# 16F.net
KiCad netlist of a schematic drawn in EasyEDA Pro
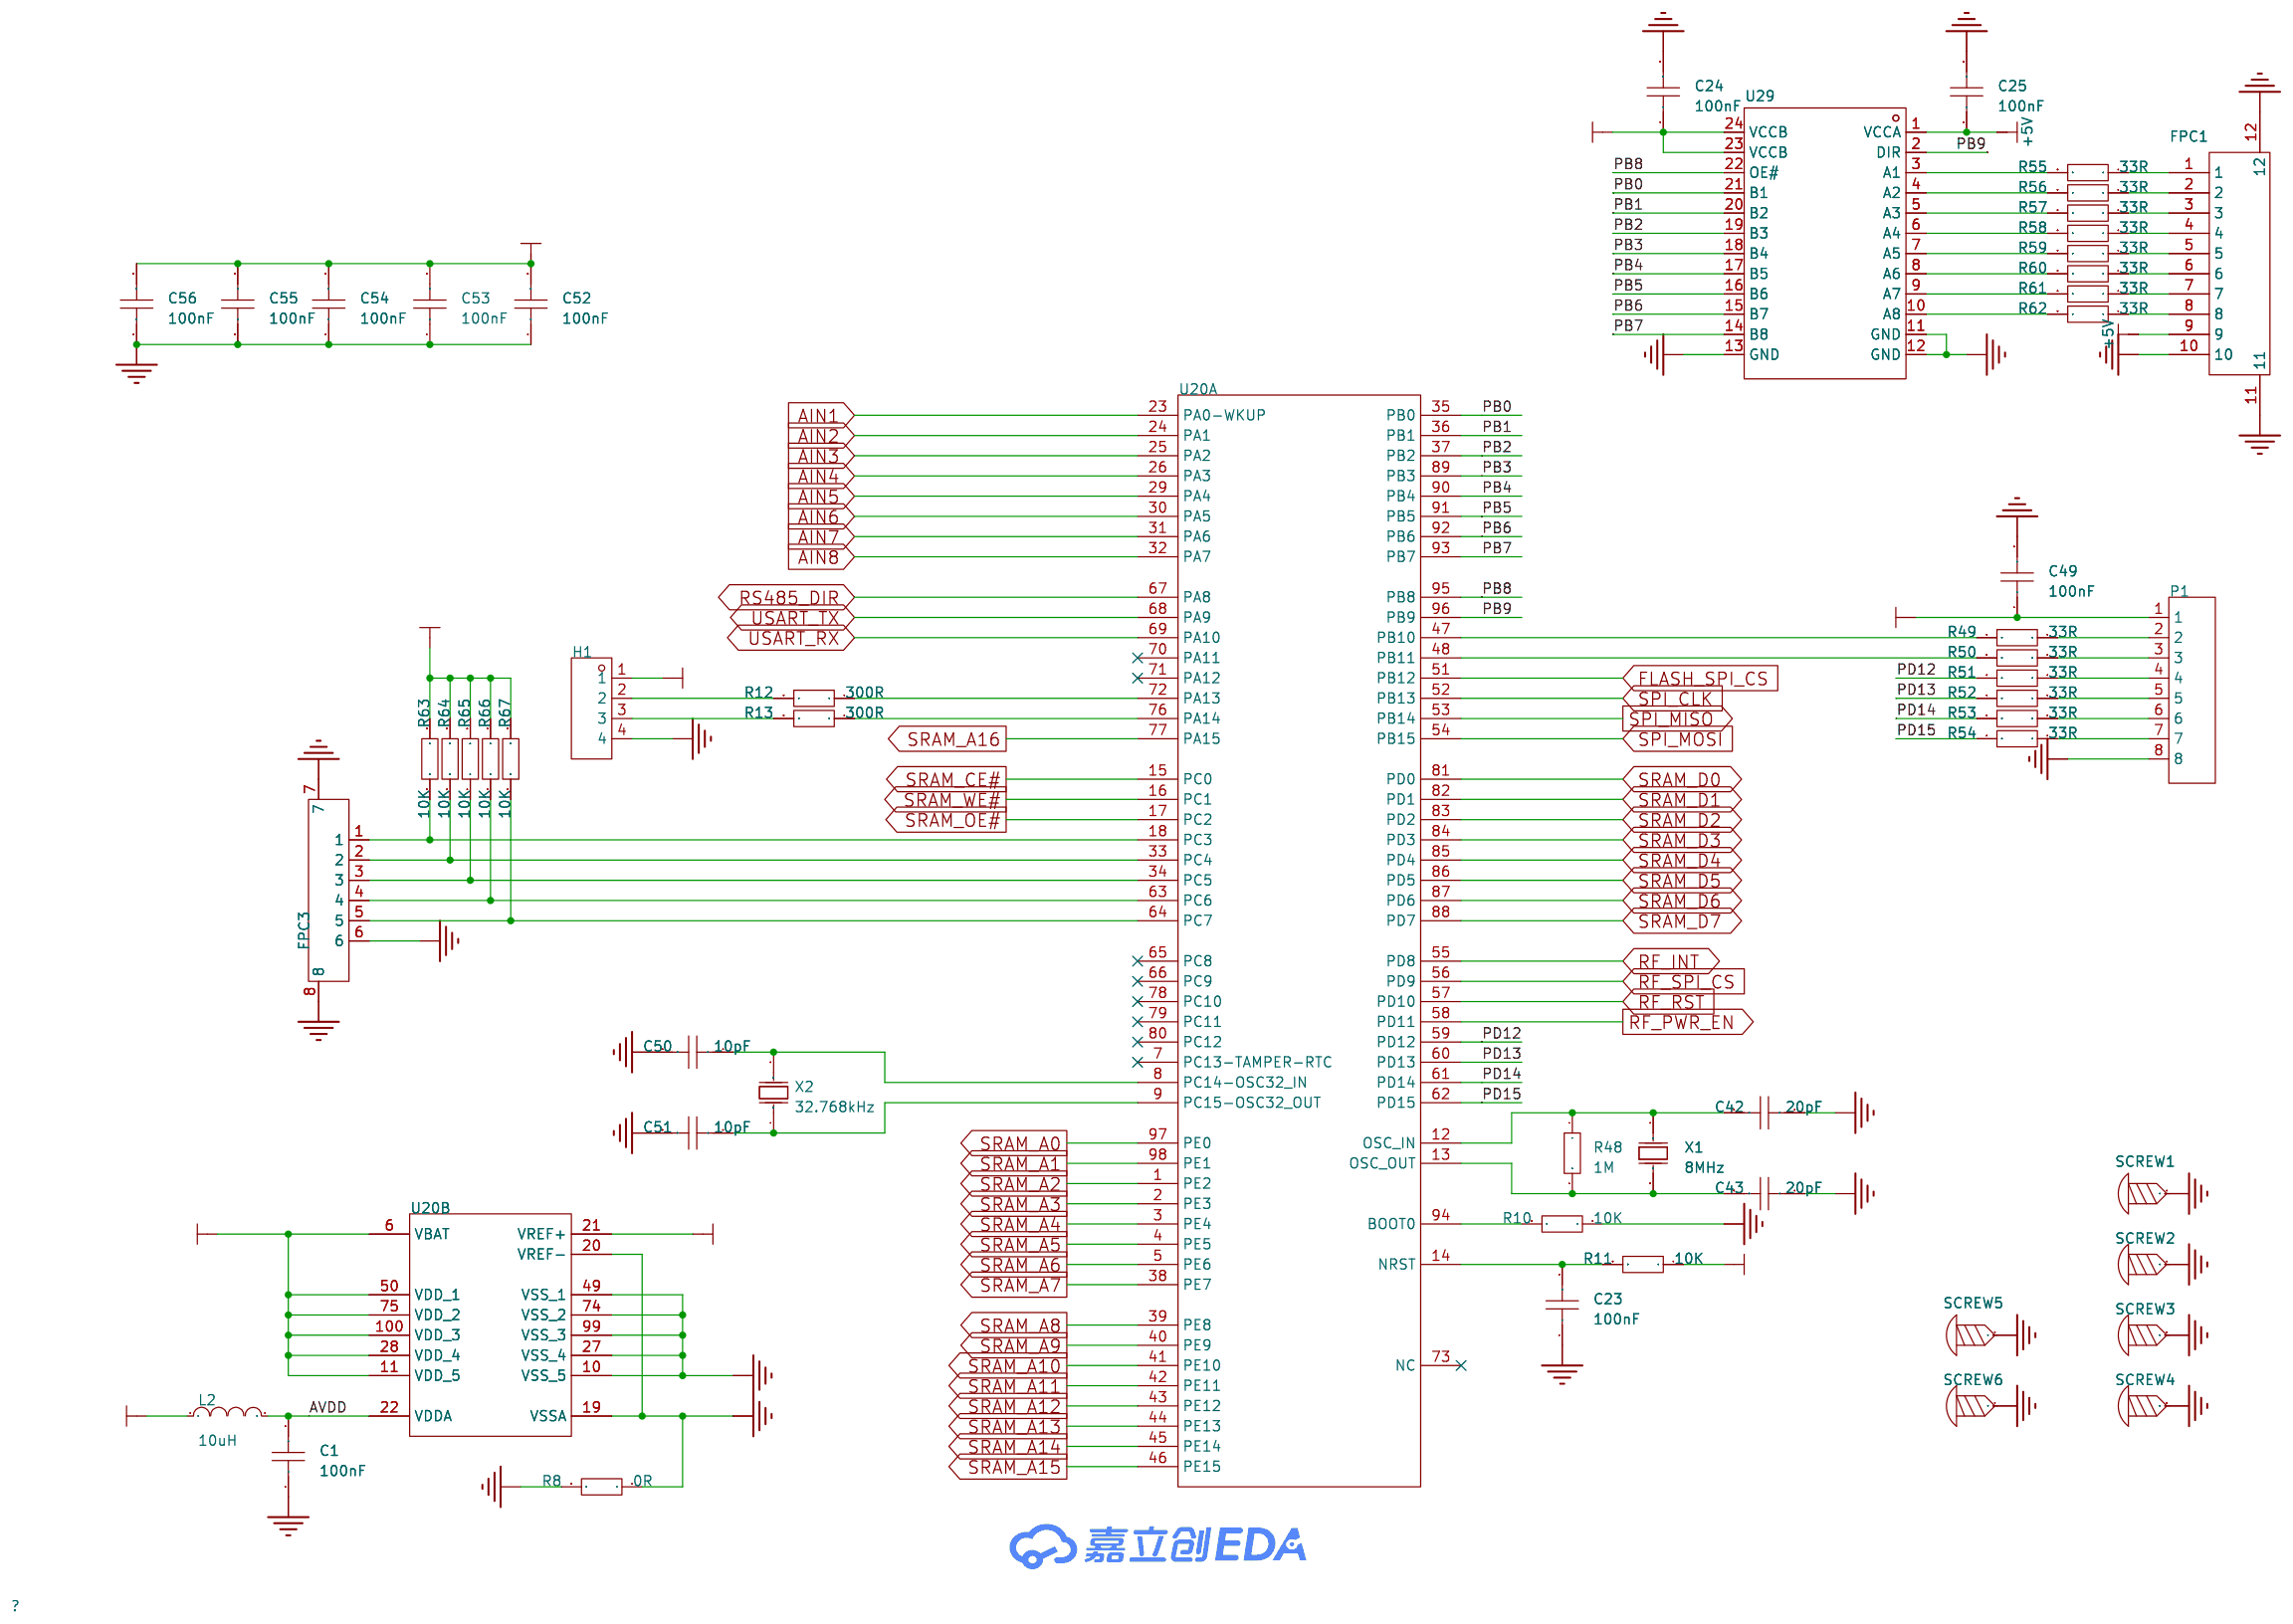
[diagram p0: MCU]
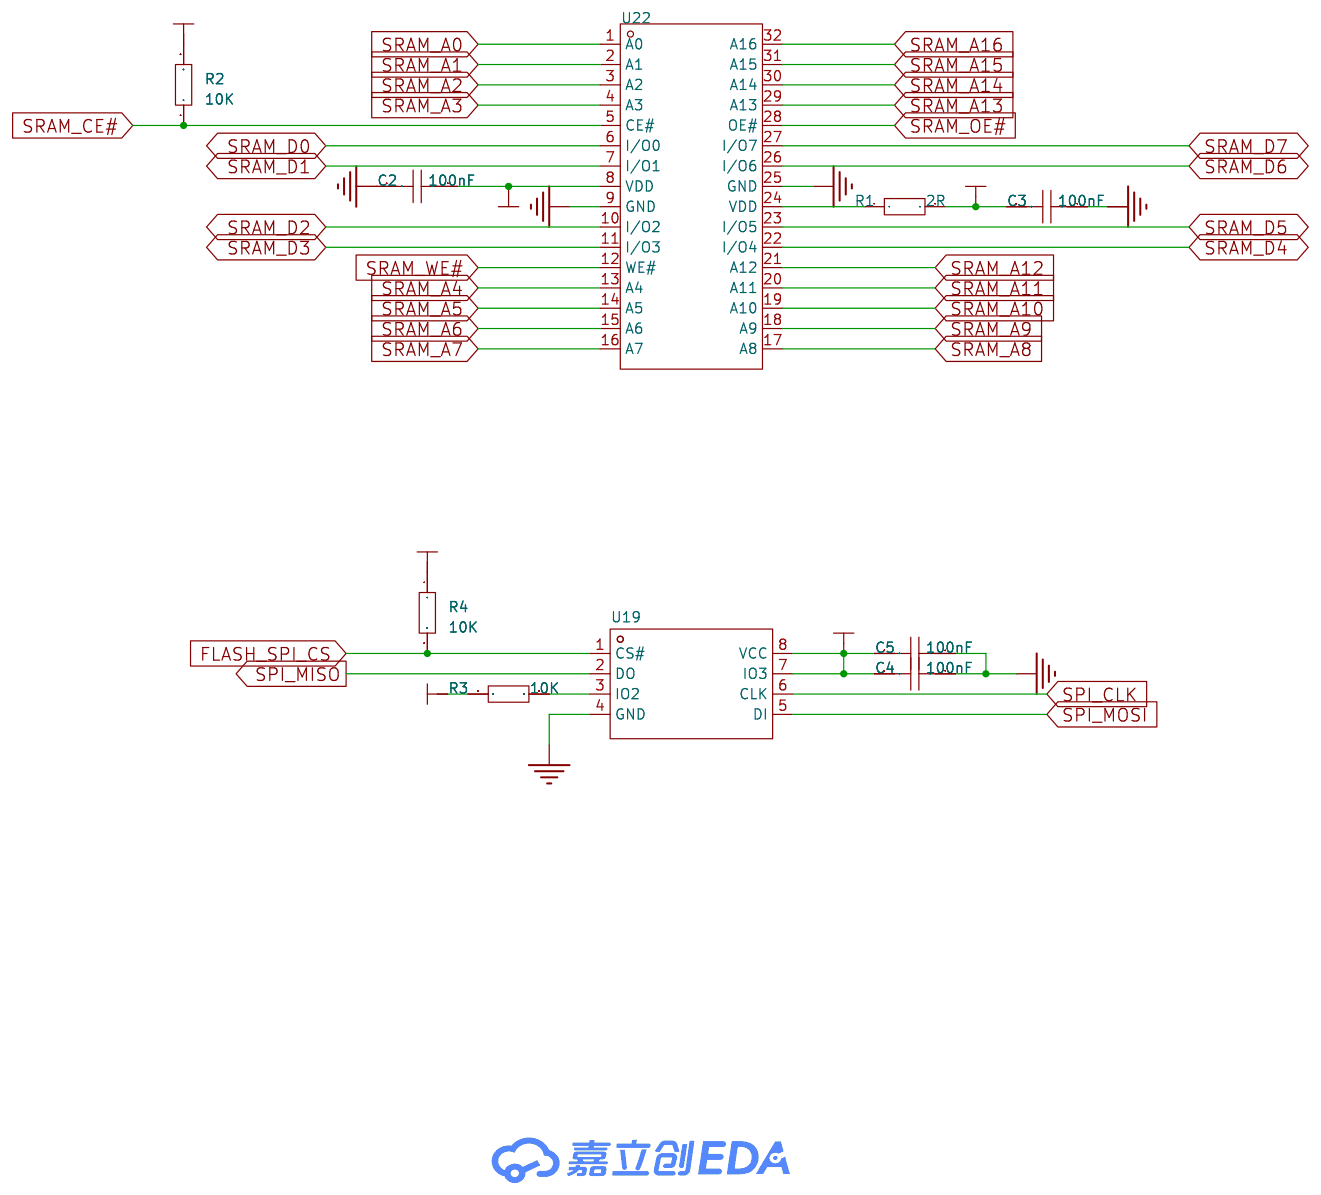
[diagram p1: MEM]
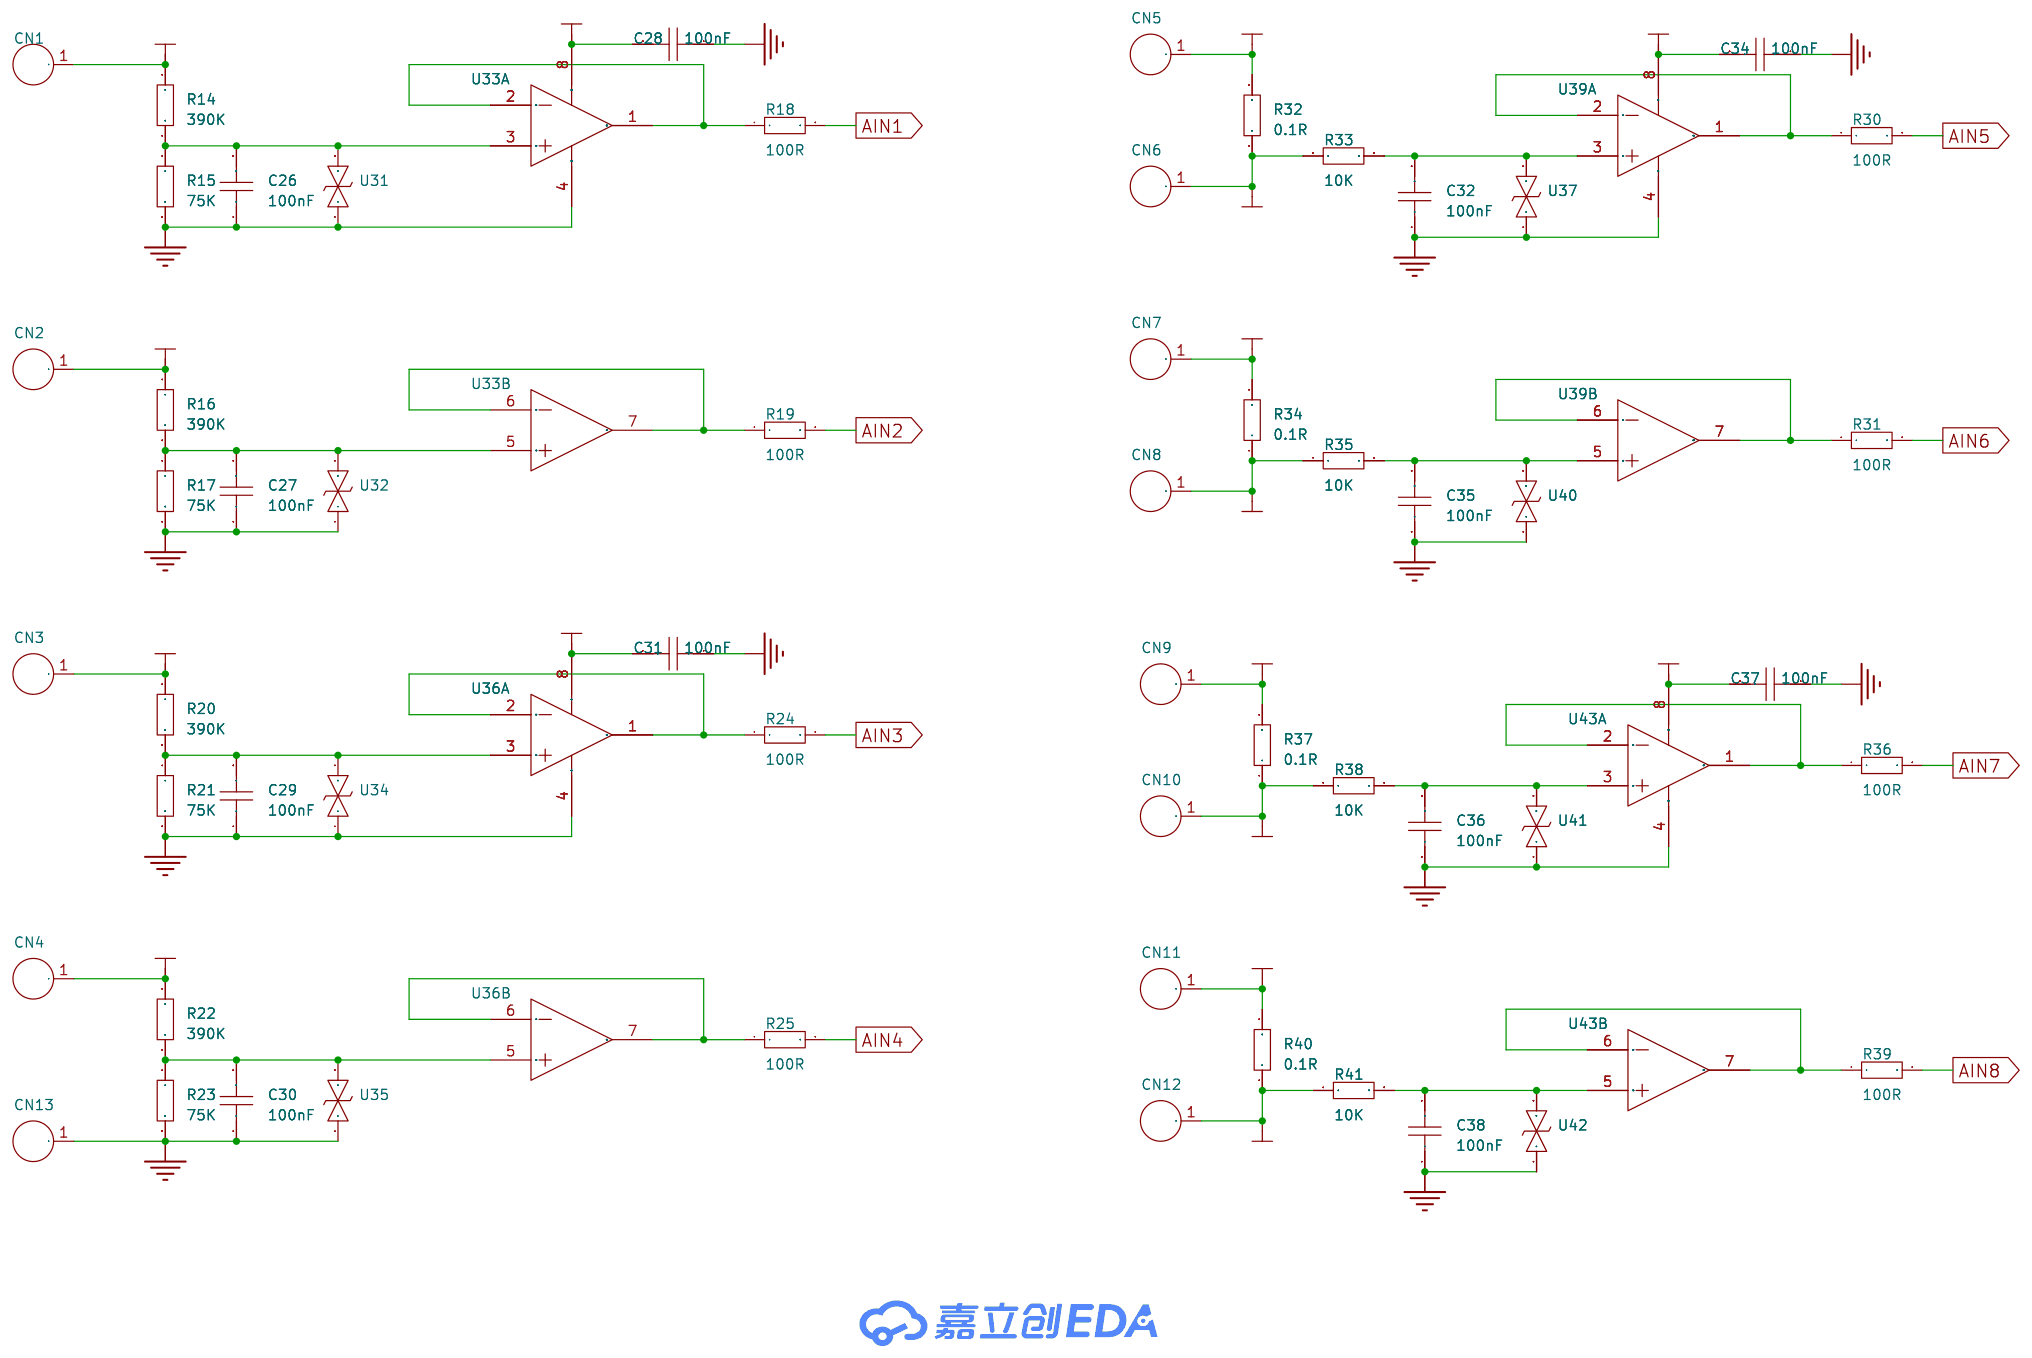
[diagram p2: AIN]
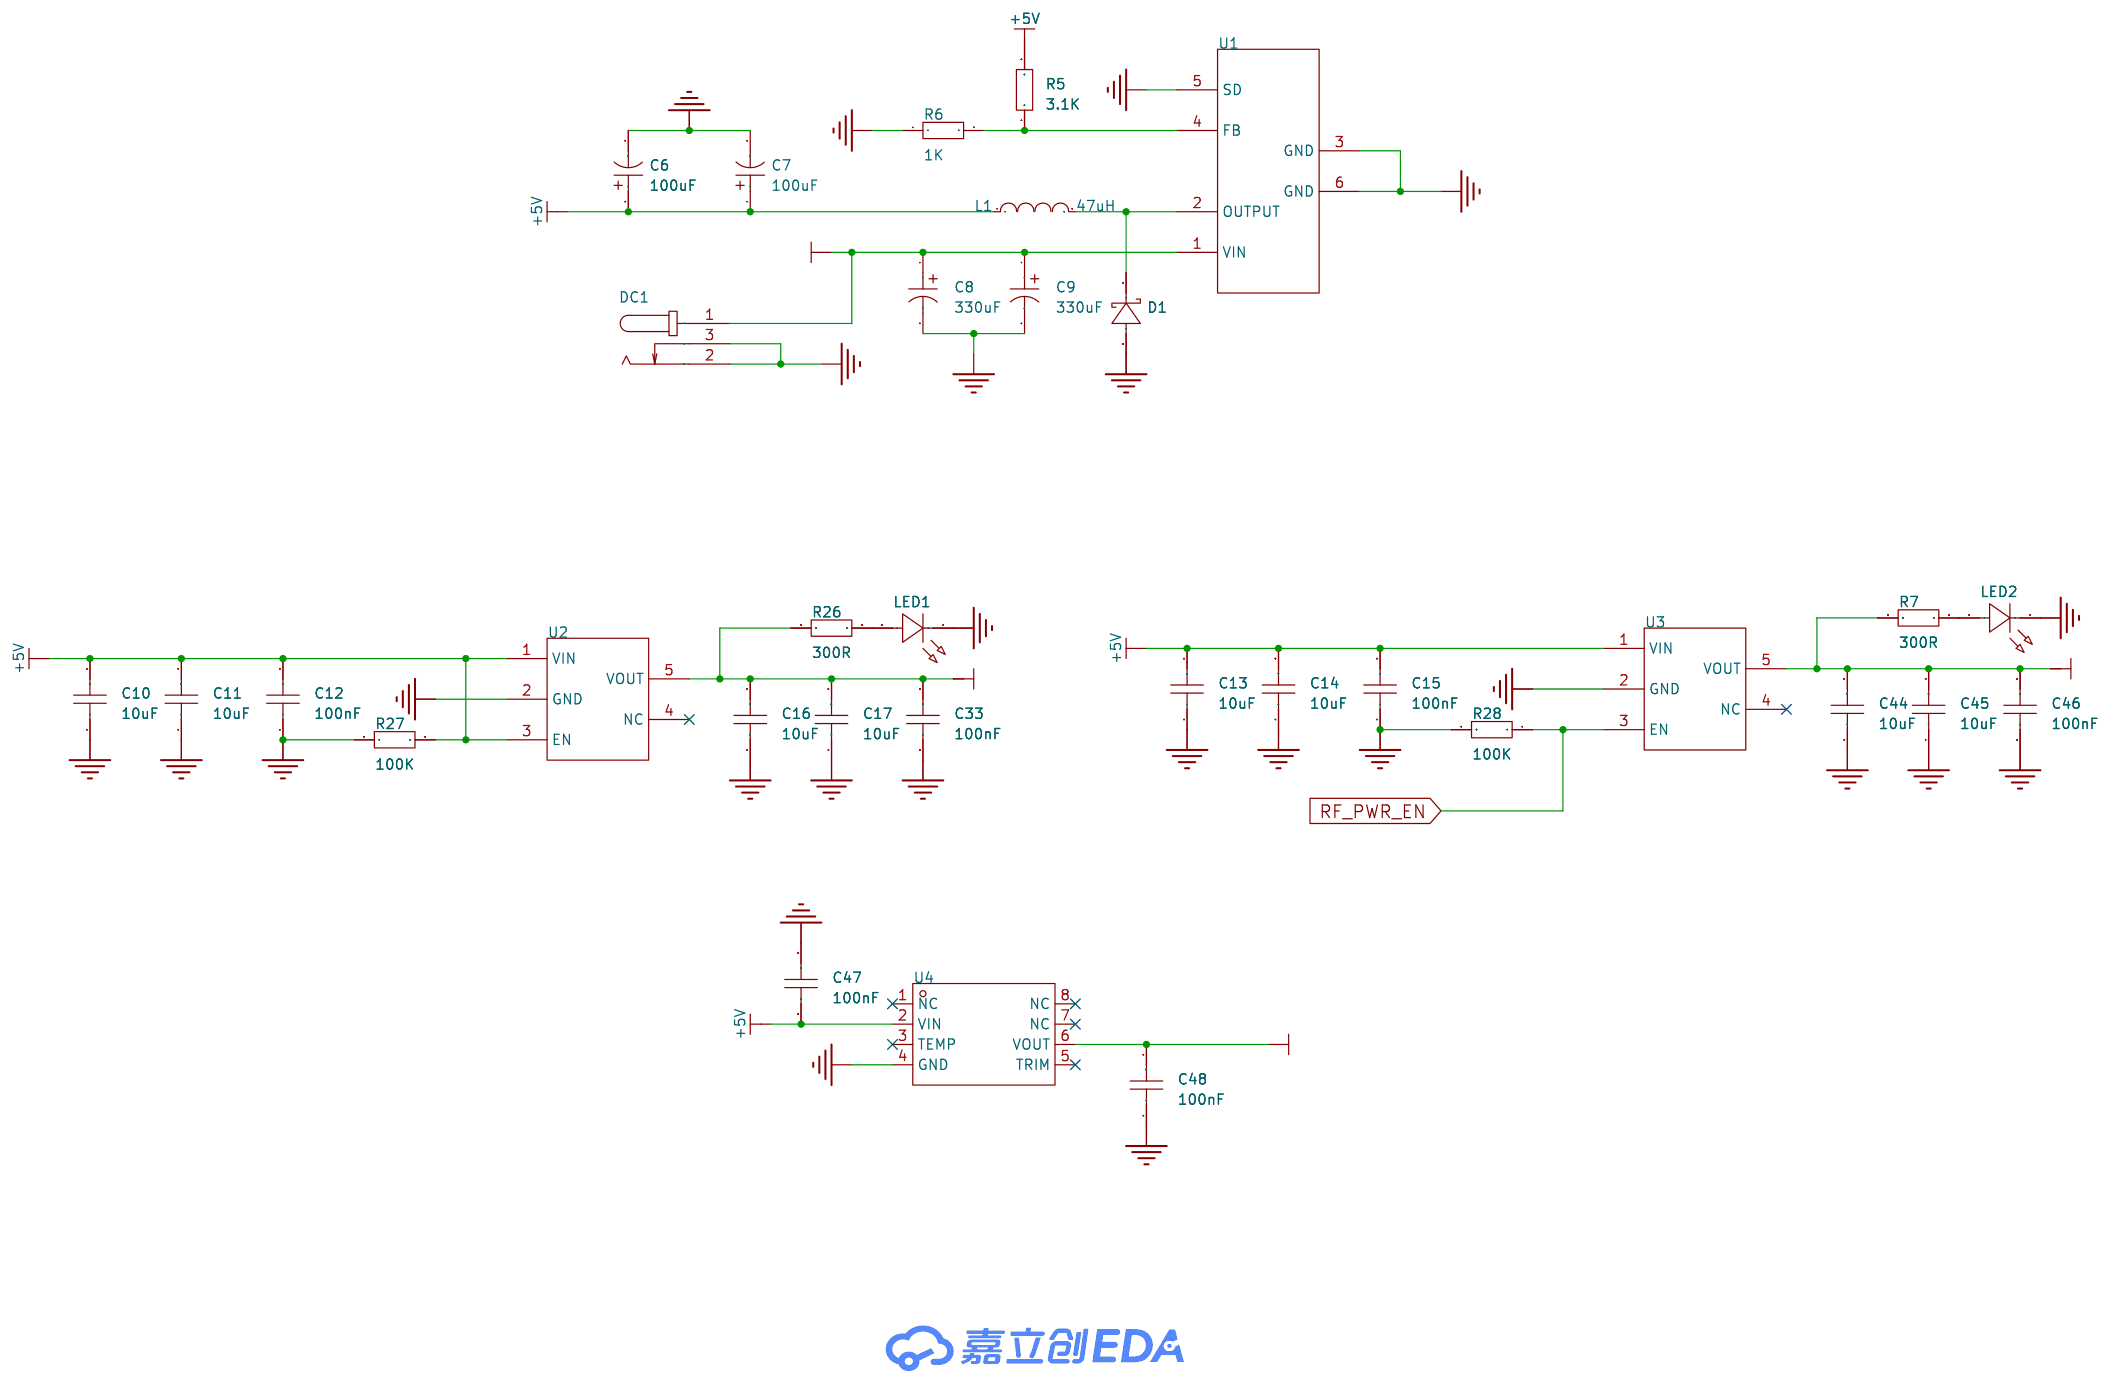
[diagram p3: POWER]
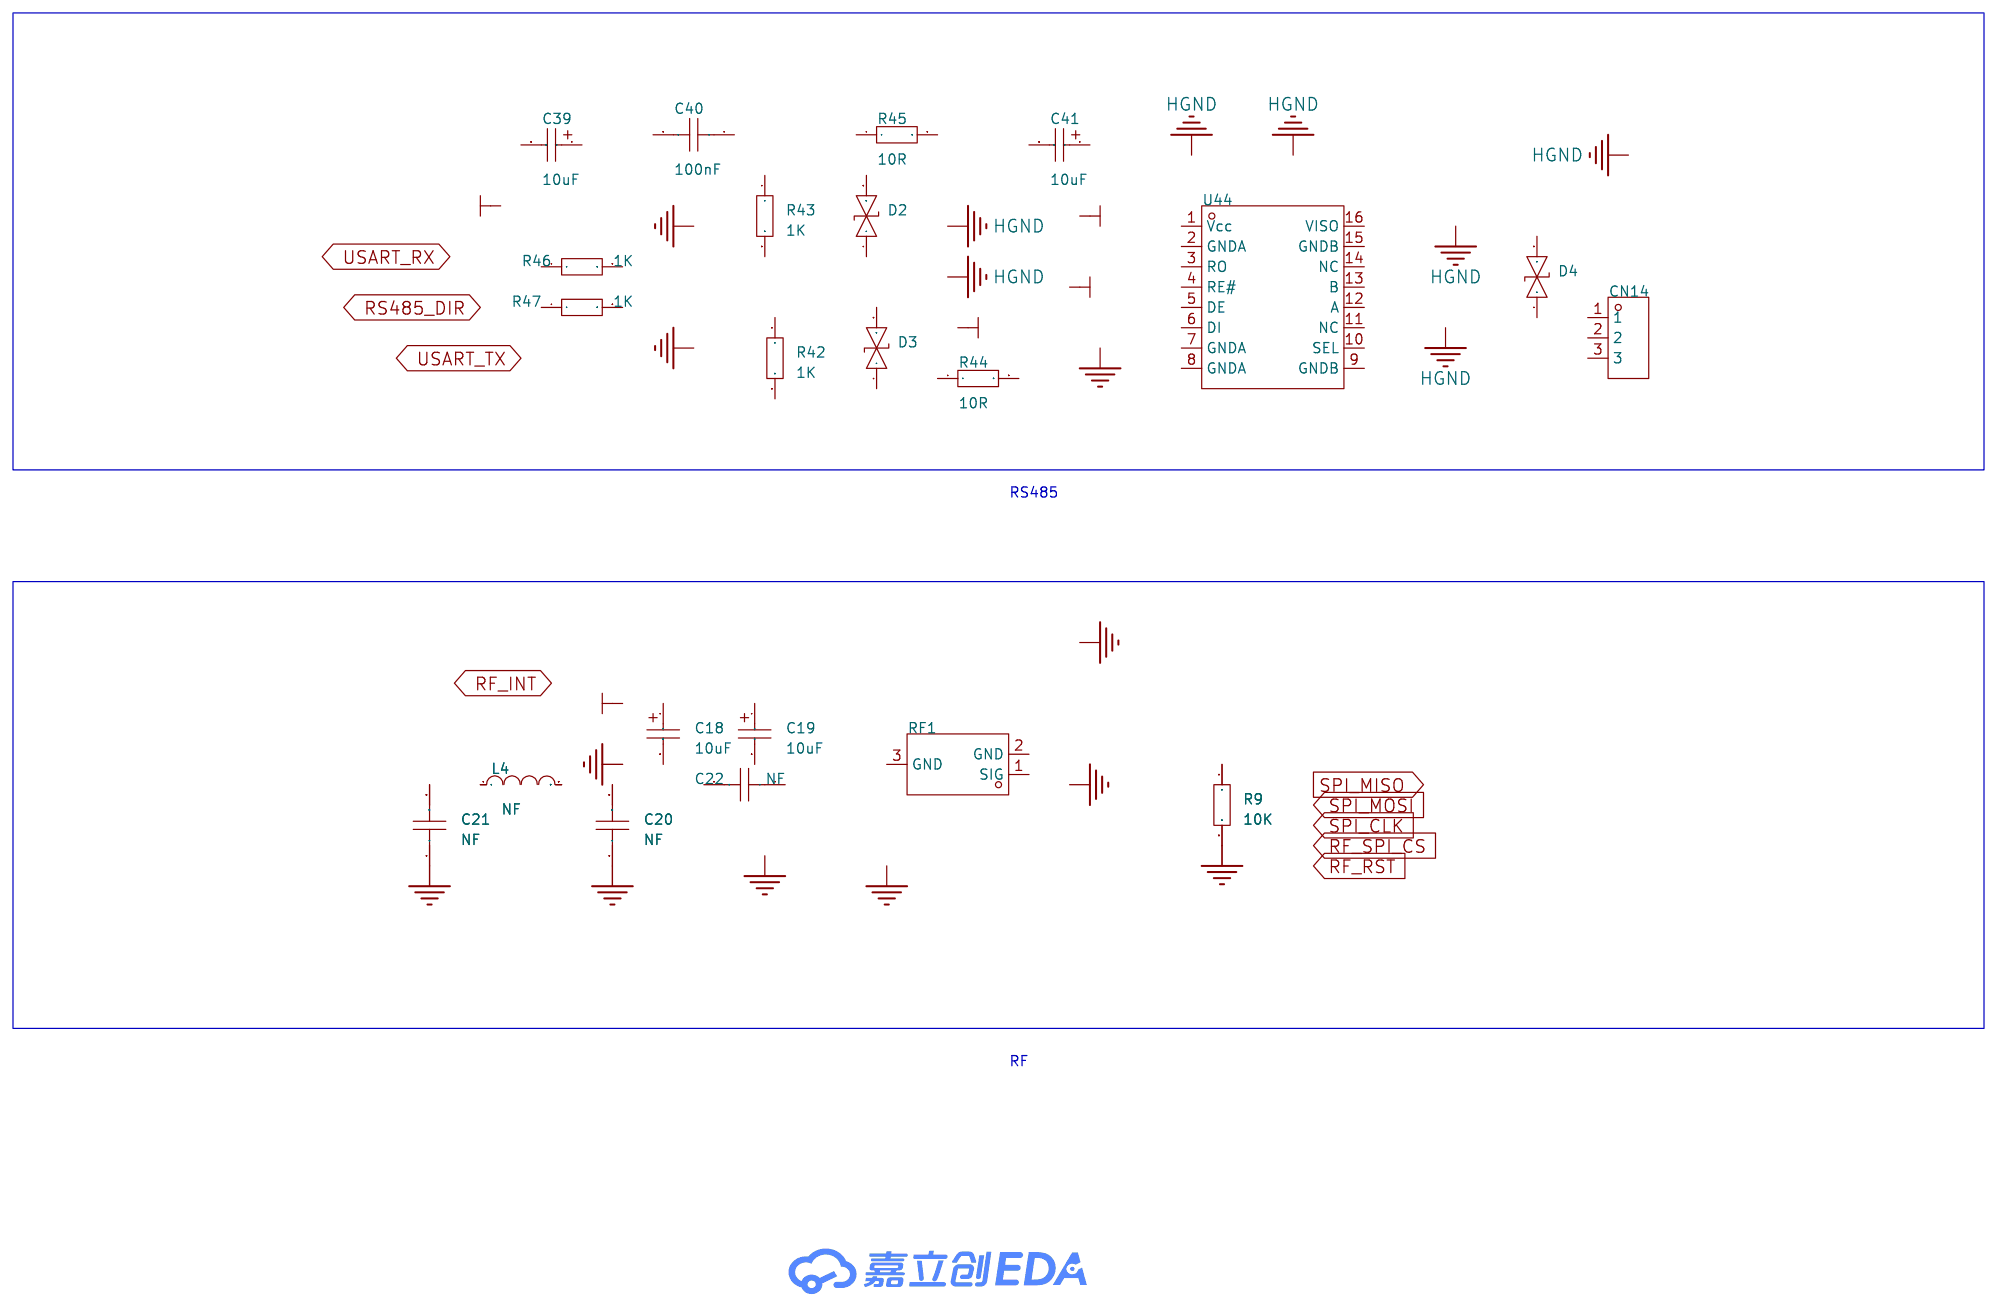
[diagram p4: RF]

(export (version "E")
  (design (tool "Eeschema 10.0.6"))
  (components
    (comp (ref "C1")
      (value "100nF")
      (footprint "easyedapro:C0805")
      (libsource (lib "easyedapro") (part "CapAcitance"))
    )
    (comp (ref "C23")
      (value "100nF")
      (footprint "easyedapro:C0805")
      (libsource (lib "easyedapro") (part "CapAcitance"))
    )
    (comp (ref "C24")
      (value "100nF")
      (footprint "easyedapro:C0805")
      (libsource (lib "easyedapro") (part "CapAcitance"))
    )
    (comp (ref "C25")
      (value "100nF")
      (footprint "easyedapro:C0805")
      (libsource (lib "easyedapro") (part "CapAcitance"))
    )
    (comp (ref "C42")
      (value "20pF")
      (footprint "easyedapro:C0805")
      (libsource (lib "easyedapro") (part "CapAcitance"))
    )
    (comp (ref "C43")
      (value "20pF")
      (footprint "easyedapro:C0805")
      (libsource (lib "easyedapro") (part "CapAcitance"))
    )
    (comp (ref "C49")
      (value "100nF")
      (footprint "easyedapro:C0805")
      (libsource (lib "easyedapro") (part "CapAcitance"))
    )
    (comp (ref "C50")
      (value "10pF")
      (footprint "easyedapro:C0805")
      (libsource (lib "easyedapro") (part "CapAcitance"))
    )
    (comp (ref "C51")
      (value "10pF")
      (footprint "easyedapro:C0805")
      (libsource (lib "easyedapro") (part "CapAcitance"))
    )
    (comp (ref "C52")
      (value "100nF")
      (footprint "easyedapro:C0805")
      (libsource (lib "easyedapro") (part "CapAcitance"))
    )
    (comp (ref "C53")
      (value "100nF")
      (footprint "easyedapro:C0805")
      (libsource (lib "easyedapro") (part "CapAcitance"))
    )
    (comp (ref "C54")
      (value "100nF")
      (footprint "easyedapro:C0805")
      (libsource (lib "easyedapro") (part "CapAcitance"))
    )
    (comp (ref "C55")
      (value "100nF")
      (footprint "easyedapro:C0805")
      (libsource (lib "easyedapro") (part "CapAcitance"))
    )
    (comp (ref "C56")
      (value "100nF")
      (footprint "easyedapro:C0805")
      (libsource (lib "easyedapro") (part "CapAcitance"))
    )
    (comp (ref "FPC1")
      (value "AFA07-S10FCA-00")
      (footprint "easyedapro:FPC-SMD_P1.00-10P_LCS-XJ-H2.0")
      (fields (field (name "Manufacturer") "JS(钜硕电子)"))
      (libsource (lib "easyedapro") (part "AFA07-S10FCA-00"))
    )
    (comp (ref "FPC3")
      (value "FPC1.0-2H-WS-6P")
      (footprint "easyedapro:FPC-SMD_6P-P1.00_FPC1.0-2H-WS")
      (libsource (lib "easyedapro") (part "FPC1.0-2H-WS-6P"))
    )
    (comp (ref "H1")
      (value "~")
      (footprint "easyedapro:HDR-TH_4P-P2.54-V-F")
      (libsource (lib "easyedapro") (part "2.54-1*4P母"))
    )
    (comp (ref "L2")
      (value "10uH")
      (footprint "easyedapro:L0805")
      (libsource (lib "easyedapro") (part "SDFL2012S100KTF"))
    )
    (comp (ref "P1")
      (value "1.25T-8AW")
      (footprint "easyedapro:CONN-TH_8P-P1.25_1.25T-1-8AW")
      (fields (field (name "Manufacturer") "BOOMELE(博穆精密)"))
      (libsource (lib "easyedapro") (part "1.25T-1-8AW"))
    )
    (comp (ref "R8") (value "0R") (footprint "easyedapro:R1210") (libsource (lib "easyedapro") (part "电阻")))
    (comp (ref "R10") (value "10K") (footprint "easyedapro:R1210") (libsource (lib "easyedapro") (part "电阻")))
    (comp (ref "R11") (value "10K") (footprint "easyedapro:R1210") (libsource (lib "easyedapro") (part "电阻")))
    (comp (ref "R12")
      (value "300R")
      (footprint "easyedapro:R1210")
      (libsource (lib "easyedapro") (part "电阻"))
    )
    (comp (ref "R13")
      (value "300R")
      (footprint "easyedapro:R1210")
      (libsource (lib "easyedapro") (part "电阻"))
    )
    (comp (ref "R48") (value "1M") (footprint "easyedapro:R1210") (libsource (lib "easyedapro") (part "电阻")))
    (comp (ref "R49") (value "33R") (footprint "easyedapro:R1210") (libsource (lib "easyedapro") (part "电阻")))
    (comp (ref "R50") (value "33R") (footprint "easyedapro:R1210") (libsource (lib "easyedapro") (part "电阻")))
    (comp (ref "R51") (value "33R") (footprint "easyedapro:R1210") (libsource (lib "easyedapro") (part "电阻")))
    (comp (ref "R52") (value "33R") (footprint "easyedapro:R1210") (libsource (lib "easyedapro") (part "电阻")))
    (comp (ref "R53") (value "33R") (footprint "easyedapro:R1210") (libsource (lib "easyedapro") (part "电阻")))
    (comp (ref "R54") (value "33R") (footprint "easyedapro:R1210") (libsource (lib "easyedapro") (part "电阻")))
    (comp (ref "R55") (value "33R") (footprint "easyedapro:R1210") (libsource (lib "easyedapro") (part "电阻")))
    (comp (ref "R56") (value "33R") (footprint "easyedapro:R1210") (libsource (lib "easyedapro") (part "电阻")))
    (comp (ref "R57") (value "33R") (footprint "easyedapro:R1210") (libsource (lib "easyedapro") (part "电阻")))
    (comp (ref "R58") (value "33R") (footprint "easyedapro:R1210") (libsource (lib "easyedapro") (part "电阻")))
    (comp (ref "R59") (value "33R") (footprint "easyedapro:R1210") (libsource (lib "easyedapro") (part "电阻")))
    (comp (ref "R60") (value "33R") (footprint "easyedapro:R1210") (libsource (lib "easyedapro") (part "电阻")))
    (comp (ref "R61") (value "33R") (footprint "easyedapro:R1210") (libsource (lib "easyedapro") (part "电阻")))
    (comp (ref "R62") (value "33R") (footprint "easyedapro:R1210") (libsource (lib "easyedapro") (part "电阻")))
    (comp (ref "R63") (value "10K") (footprint "easyedapro:R1210") (libsource (lib "easyedapro") (part "电阻")))
    (comp (ref "R64") (value "10K") (footprint "easyedapro:R1210") (libsource (lib "easyedapro") (part "电阻")))
    (comp (ref "R65") (value "10K") (footprint "easyedapro:R1210") (libsource (lib "easyedapro") (part "电阻")))
    (comp (ref "R66") (value "10K") (footprint "easyedapro:R1210") (libsource (lib "easyedapro") (part "电阻")))
    (comp (ref "R67") (value "10K") (footprint "easyedapro:R1210") (libsource (lib "easyedapro") (part "电阻")))
    (comp (ref "SCREW1")
      (value "~")
      (footprint "easyedapro:M2螺丝")
      (libsource (lib "easyedapro") (part "螺丝孔"))
    )
    (comp (ref "SCREW2")
      (value "~")
      (footprint "easyedapro:M2螺丝")
      (libsource (lib "easyedapro") (part "螺丝孔"))
    )
    (comp (ref "SCREW3")
      (value "~")
      (footprint "easyedapro:M2螺丝")
      (libsource (lib "easyedapro") (part "螺丝孔"))
    )
    (comp (ref "SCREW4")
      (value "~")
      (footprint "easyedapro:M2螺丝")
      (libsource (lib "easyedapro") (part "螺丝孔"))
    )
    (comp (ref "SCREW5")
      (value "~")
      (footprint "easyedapro:M2螺丝")
      (libsource (lib "easyedapro") (part "螺丝孔"))
    )
    (comp (ref "SCREW6")
      (value "~")
      (footprint "easyedapro:M2螺丝")
      (libsource (lib "easyedapro") (part "螺丝孔"))
    )
    (comp (ref "U20")
      (value "STM32F103VBT6")
      (footprint "easyedapro:LQFP-100_L14.0-W14.0-P0.50-LS16.0-BL")
      (fields (field (name "Manufacturer") "ST(意法半导体)"))
      (libsource (lib "easyedapro") (part "STM32F103VBT6"))
    )
    (comp (ref "U29")
      (value "SN74LVC8T245PWR")
      (footprint "easyedapro:TSSOP-24_L7.8-W4.4-P0.65-LS6.4-BL")
      (fields (field (name "Manufacturer") "TI(德州仪器)"))
      (libsource (lib "easyedapro") (part "SN74LVC8T245PWR"))
    )
    (comp (ref "X1")
      (value "8MHz")
      (footprint "easyedapro:CRYSTAL-SMD_L5.0-W3.2")
      (fields (field (name "Manufacturer Part") "X50328MSB2GI") (field (name "Manufacturer") "YXC(扬兴晶振)"))
      (libsource (lib "easyedapro") (part "X50328MSB2GI"))
    )
    (comp (ref "X2")
      (value "32.768kHz")
      (footprint "easyedapro:OSC-SMD_L3.2-W1.5")
      (fields (field (name "Manufacturer Part") "Q13FC1350000300") (field (name "Manufacturer") "EPSON(爱普生)"))
      (libsource (lib "easyedapro") (part "FC-13532.768KHZ9PF20PPM"))
    )
    (comp (ref "C2")
      (value "100nF")
      (footprint "easyedapro:C0805")
      (libsource (lib "easyedapro") (part "CapAcitance"))
    )
    (comp (ref "C3")
      (value "100nF")
      (footprint "easyedapro:C0805")
      (libsource (lib "easyedapro") (part "CapAcitance"))
    )
    (comp (ref "C4")
      (value "100nF")
      (footprint "easyedapro:C0805")
      (libsource (lib "easyedapro") (part "CapAcitance"))
    )
    (comp (ref "C5")
      (value "100nF")
      (footprint "easyedapro:C0805")
      (libsource (lib "easyedapro") (part "CapAcitance"))
    )
    (comp (ref "R1") (value "2R") (footprint "easyedapro:R1210") (libsource (lib "easyedapro") (part "电阻")))
    (comp (ref "R2") (value "10K") (footprint "easyedapro:R1210") (libsource (lib "easyedapro") (part "电阻")))
    (comp (ref "R3") (value "10K") (footprint "easyedapro:R1210") (libsource (lib "easyedapro") (part "电阻")))
    (comp (ref "R4") (value "10K") (footprint "easyedapro:R1210") (libsource (lib "easyedapro") (part "电阻")))
    (comp (ref "U19")
      (value "W25Q128JVSIQ")
      (footprint "easyedapro:SOIC-8_L5.3-W5.3-P1.27-LS8.0-BL")
      (fields (field (name "Manufacturer") "WINBOND(华邦)"))
      (libsource (lib "easyedapro") (part "W25Q128JVSIQTR"))
    )
    (comp (ref "U22")
      (value "IS63WV1288DBLL-10TLI")
      (footprint "easyedapro:TSOPII-32_L21.0-W10.2-P1.27-LS11.8-BL")
      (fields (field (name "Manufacturer") "ISSI(美国芯成)"))
      (libsource (lib "easyedapro") (part "IS63WV1288DBLL-10TLI"))
    )
    (comp (ref "C26")
      (value "100nF")
      (footprint "easyedapro:C0805")
      (libsource (lib "easyedapro") (part "CapAcitance"))
    )
    (comp (ref "C27")
      (value "100nF")
      (footprint "easyedapro:C0805")
      (libsource (lib "easyedapro") (part "CapAcitance"))
    )
    (comp (ref "C28")
      (value "100nF")
      (footprint "easyedapro:C0805")
      (libsource (lib "easyedapro") (part "CapAcitance"))
    )
    (comp (ref "C29")
      (value "100nF")
      (footprint "easyedapro:C0805")
      (libsource (lib "easyedapro") (part "CapAcitance"))
    )
    (comp (ref "C30")
      (value "100nF")
      (footprint "easyedapro:C0805")
      (libsource (lib "easyedapro") (part "CapAcitance"))
    )
    (comp (ref "C31")
      (value "100nF")
      (footprint "easyedapro:C0805")
      (libsource (lib "easyedapro") (part "CapAcitance"))
    )
    (comp (ref "C32")
      (value "100nF")
      (footprint "easyedapro:C0805")
      (libsource (lib "easyedapro") (part "CapAcitance"))
    )
    (comp (ref "C34")
      (value "100nF")
      (footprint "easyedapro:C0805")
      (libsource (lib "easyedapro") (part "CapAcitance"))
    )
    (comp (ref "C35")
      (value "100nF")
      (footprint "easyedapro:C0805")
      (libsource (lib "easyedapro") (part "CapAcitance"))
    )
    (comp (ref "C36")
      (value "100nF")
      (footprint "easyedapro:C0805")
      (libsource (lib "easyedapro") (part "CapAcitance"))
    )
    (comp (ref "C37")
      (value "100nF")
      (footprint "easyedapro:C0805")
      (libsource (lib "easyedapro") (part "CapAcitance"))
    )
    (comp (ref "C38")
      (value "100nF")
      (footprint "easyedapro:C0805")
      (libsource (lib "easyedapro") (part "CapAcitance"))
    )
    (comp (ref "CN1")
      (value "8730")
      (footprint "easyedapro:CONN-TH_8730")
      (fields (field (name "Manufacturer") "Keystone"))
      (libsource (lib "easyedapro") (part "8730"))
    )
    (comp (ref "CN2")
      (value "8730")
      (footprint "easyedapro:CONN-TH_8730")
      (fields (field (name "Manufacturer") "Keystone"))
      (libsource (lib "easyedapro") (part "8730"))
    )
    (comp (ref "CN3")
      (value "8730")
      (footprint "easyedapro:CONN-TH_8730")
      (fields (field (name "Manufacturer") "Keystone"))
      (libsource (lib "easyedapro") (part "8730"))
    )
    (comp (ref "CN4")
      (value "8730")
      (footprint "easyedapro:CONN-TH_8730")
      (fields (field (name "Manufacturer") "Keystone"))
      (libsource (lib "easyedapro") (part "8730"))
    )
    (comp (ref "CN5")
      (value "8730")
      (footprint "easyedapro:CONN-TH_8730")
      (fields (field (name "Manufacturer") "Keystone"))
      (libsource (lib "easyedapro") (part "8730"))
    )
    (comp (ref "CN6")
      (value "8730")
      (footprint "easyedapro:CONN-TH_8730")
      (fields (field (name "Manufacturer") "Keystone"))
      (libsource (lib "easyedapro") (part "8730"))
    )
    (comp (ref "CN7")
      (value "8730")
      (footprint "easyedapro:CONN-TH_8730")
      (fields (field (name "Manufacturer") "Keystone"))
      (libsource (lib "easyedapro") (part "8730"))
    )
    (comp (ref "CN8")
      (value "8730")
      (footprint "easyedapro:CONN-TH_8730")
      (fields (field (name "Manufacturer") "Keystone"))
      (libsource (lib "easyedapro") (part "8730"))
    )
    (comp (ref "CN9")
      (value "8730")
      (footprint "easyedapro:CONN-TH_8730")
      (fields (field (name "Manufacturer") "Keystone"))
      (libsource (lib "easyedapro") (part "8730"))
    )
    (comp (ref "CN10")
      (value "8730")
      (footprint "easyedapro:CONN-TH_8730")
      (fields (field (name "Manufacturer") "Keystone"))
      (libsource (lib "easyedapro") (part "8730"))
    )
    (comp (ref "CN11")
      (value "8730")
      (footprint "easyedapro:CONN-TH_8730")
      (fields (field (name "Manufacturer") "Keystone"))
      (libsource (lib "easyedapro") (part "8730"))
    )
    (comp (ref "CN12")
      (value "8730")
      (footprint "easyedapro:CONN-TH_8730")
      (fields (field (name "Manufacturer") "Keystone"))
      (libsource (lib "easyedapro") (part "8730"))
    )
    (comp (ref "CN13")
      (value "8730")
      (footprint "easyedapro:CONN-TH_8730")
      (fields (field (name "Manufacturer") "Keystone"))
      (libsource (lib "easyedapro") (part "8730"))
    )
    (comp (ref "R14")
      (value "390K")
      (footprint "easyedapro:R1210")
      (libsource (lib "easyedapro") (part "电阻"))
    )
    (comp (ref "R15") (value "75K") (footprint "easyedapro:R1210") (libsource (lib "easyedapro") (part "电阻")))
    (comp (ref "R16")
      (value "390K")
      (footprint "easyedapro:R1210")
      (libsource (lib "easyedapro") (part "电阻"))
    )
    (comp (ref "R17") (value "75K") (footprint "easyedapro:R1210") (libsource (lib "easyedapro") (part "电阻")))
    (comp (ref "R18")
      (value "100R")
      (footprint "easyedapro:R1210")
      (libsource (lib "easyedapro") (part "电阻"))
    )
    (comp (ref "R19")
      (value "100R")
      (footprint "easyedapro:R1210")
      (libsource (lib "easyedapro") (part "电阻"))
    )
    (comp (ref "R20")
      (value "390K")
      (footprint "easyedapro:R1210")
      (libsource (lib "easyedapro") (part "电阻"))
    )
    (comp (ref "R21") (value "75K") (footprint "easyedapro:R1210") (libsource (lib "easyedapro") (part "电阻")))
    (comp (ref "R22")
      (value "390K")
      (footprint "easyedapro:R1210")
      (libsource (lib "easyedapro") (part "电阻"))
    )
    (comp (ref "R23") (value "75K") (footprint "easyedapro:R1210") (libsource (lib "easyedapro") (part "电阻")))
    (comp (ref "R24")
      (value "100R")
      (footprint "easyedapro:R1210")
      (libsource (lib "easyedapro") (part "电阻"))
    )
    (comp (ref "R25")
      (value "100R")
      (footprint "easyedapro:R1210")
      (libsource (lib "easyedapro") (part "电阻"))
    )
    (comp (ref "R30")
      (value "100R")
      (footprint "easyedapro:R1210")
      (libsource (lib "easyedapro") (part "电阻"))
    )
    (comp (ref "R31")
      (value "100R")
      (footprint "easyedapro:R1210")
      (libsource (lib "easyedapro") (part "电阻"))
    )
    (comp (ref "R32")
      (value "0.1R")
      (footprint "easyedapro:R1210")
      (libsource (lib "easyedapro") (part "电阻"))
    )
    (comp (ref "R33") (value "10K") (footprint "easyedapro:R1210") (libsource (lib "easyedapro") (part "电阻")))
    (comp (ref "R34")
      (value "0.1R")
      (footprint "easyedapro:R1210")
      (libsource (lib "easyedapro") (part "电阻"))
    )
    (comp (ref "R35") (value "10K") (footprint "easyedapro:R1210") (libsource (lib "easyedapro") (part "电阻")))
    (comp (ref "R36")
      (value "100R")
      (footprint "easyedapro:R1210")
      (libsource (lib "easyedapro") (part "电阻"))
    )
    (comp (ref "R37")
      (value "0.1R")
      (footprint "easyedapro:R1210")
      (libsource (lib "easyedapro") (part "电阻"))
    )
    (comp (ref "R38") (value "10K") (footprint "easyedapro:R1210") (libsource (lib "easyedapro") (part "电阻")))
    (comp (ref "R39")
      (value "100R")
      (footprint "easyedapro:R1210")
      (libsource (lib "easyedapro") (part "电阻"))
    )
    (comp (ref "R40")
      (value "0.1R")
      (footprint "easyedapro:R1210")
      (libsource (lib "easyedapro") (part "电阻"))
    )
    (comp (ref "R41") (value "10K") (footprint "easyedapro:R1210") (libsource (lib "easyedapro") (part "电阻")))
    (comp (ref "U31")
      (value "BV-D505ZC-ES")
      (footprint "easyedapro:SOD-523_L1.2-W0.8-LS1.6-BI")
      (fields (field (name "Manufacturer") "ElecSuper(静芯微)"))
      (libsource (lib "easyedapro") (part "BV-D505ZC-ES"))
    )
    (comp (ref "U32")
      (value "BV-D505ZC-ES")
      (footprint "easyedapro:SOD-523_L1.2-W0.8-LS1.6-BI")
      (fields (field (name "Manufacturer") "ElecSuper(静芯微)"))
      (libsource (lib "easyedapro") (part "BV-D505ZC-ES"))
    )
    (comp (ref "U33")
      (value "LMV358IDR(UMW)")
      (footprint "easyedapro:SOP-8_L4.9-W3.9-P1.27-LS6.0-BL")
      (fields (field (name "Manufacturer") "UMW(友台半导体)"))
      (libsource (lib "easyedapro") (part "LMV358IDR_C3008587"))
    )
    (comp (ref "U34")
      (value "BV-D505ZC-ES")
      (footprint "easyedapro:SOD-523_L1.2-W0.8-LS1.6-BI")
      (fields (field (name "Manufacturer") "ElecSuper(静芯微)"))
      (libsource (lib "easyedapro") (part "BV-D505ZC-ES"))
    )
    (comp (ref "U35")
      (value "BV-D505ZC-ES")
      (footprint "easyedapro:SOD-523_L1.2-W0.8-LS1.6-BI")
      (fields (field (name "Manufacturer") "ElecSuper(静芯微)"))
      (libsource (lib "easyedapro") (part "BV-D505ZC-ES"))
    )
    (comp (ref "U36")
      (value "LMV358IDR(UMW)")
      (footprint "easyedapro:SOP-8_L4.9-W3.9-P1.27-LS6.0-BL")
      (fields (field (name "Manufacturer") "UMW(友台半导体)"))
      (libsource (lib "easyedapro") (part "LMV358IDR_C3008587"))
    )
    (comp (ref "U37")
      (value "BV-D505ZC-ES")
      (footprint "easyedapro:SOD-523_L1.2-W0.8-LS1.6-BI")
      (fields (field (name "Manufacturer") "ElecSuper(静芯微)"))
      (libsource (lib "easyedapro") (part "BV-D505ZC-ES"))
    )
    (comp (ref "U39")
      (value "LMV358IDR(UMW)")
      (footprint "easyedapro:SOP-8_L4.9-W3.9-P1.27-LS6.0-BL")
      (fields (field (name "Manufacturer") "UMW(友台半导体)"))
      (libsource (lib "easyedapro") (part "LMV358IDR_C3008587"))
    )
    (comp (ref "U40")
      (value "BV-D505ZC-ES")
      (footprint "easyedapro:SOD-523_L1.2-W0.8-LS1.6-BI")
      (fields (field (name "Manufacturer") "ElecSuper(静芯微)"))
      (libsource (lib "easyedapro") (part "BV-D505ZC-ES"))
    )
    (comp (ref "U41")
      (value "BV-D505ZC-ES")
      (footprint "easyedapro:SOD-523_L1.2-W0.8-LS1.6-BI")
      (fields (field (name "Manufacturer") "ElecSuper(静芯微)"))
      (libsource (lib "easyedapro") (part "BV-D505ZC-ES"))
    )
    (comp (ref "U42")
      (value "BV-D505ZC-ES")
      (footprint "easyedapro:SOD-523_L1.2-W0.8-LS1.6-BI")
      (fields (field (name "Manufacturer") "ElecSuper(静芯微)"))
      (libsource (lib "easyedapro") (part "BV-D505ZC-ES"))
    )
    (comp (ref "U43")
      (value "LMV358IDR(UMW)")
      (footprint "easyedapro:SOP-8_L4.9-W3.9-P1.27-LS6.0-BL")
      (fields (field (name "Manufacturer") "UMW(友台半导体)"))
      (libsource (lib "easyedapro") (part "LMV358IDR_C3008587"))
    )
    (comp (ref "C6")
      (value "100uF")
      (footprint "easyedapro:CAP-SMD_BD6.3-L6.6-W6.6-LS7.3-FD-H7.7")
      (fields (field (name "Manufacturer Part") "JVJ50V100M6x8") (field (name "Manufacturer") "捷而瑞"))
      (libsource (lib "easyedapro") (part "JVJ50V100M6X8"))
    )
    (comp (ref "C7")
      (value "100uF")
      (footprint "easyedapro:CAP-SMD_BD6.3-L6.6-W6.6-LS7.3-FD-H7.7")
      (fields (field (name "Manufacturer Part") "JVJ50V100M6x8") (field (name "Manufacturer") "捷而瑞"))
      (libsource (lib "easyedapro") (part "JVJ50V100M6X8"))
    )
    (comp (ref "C8")
      (value "330uF")
      (footprint "easyedapro:CAP-SMD_BD10.0-L10.3-W10.3-FD-LS11.0")
      (fields (field (name "Manufacturer Part") "JVJ50V330M10x10") (field (name "Manufacturer") "捷而瑞"))
      (libsource (lib "easyedapro") (part "JVJ50V330M10X10"))
    )
    (comp (ref "C9")
      (value "330uF")
      (footprint "easyedapro:CAP-SMD_BD10.0-L10.3-W10.3-FD-LS11.0")
      (fields (field (name "Manufacturer Part") "JVJ50V330M10x10") (field (name "Manufacturer") "捷而瑞"))
      (libsource (lib "easyedapro") (part "JVJ50V330M10X10"))
    )
    (comp (ref "C10")
      (value "10uF")
      (footprint "easyedapro:C0805")
      (libsource (lib "easyedapro") (part "CapAcitance"))
    )
    (comp (ref "C11")
      (value "10uF")
      (footprint "easyedapro:C0805")
      (libsource (lib "easyedapro") (part "CapAcitance"))
    )
    (comp (ref "C12")
      (value "100nF")
      (footprint "easyedapro:C0805")
      (libsource (lib "easyedapro") (part "CapAcitance"))
    )
    (comp (ref "C13")
      (value "10uF")
      (footprint "easyedapro:C0805")
      (libsource (lib "easyedapro") (part "CapAcitance"))
    )
    (comp (ref "C14")
      (value "10uF")
      (footprint "easyedapro:C0805")
      (libsource (lib "easyedapro") (part "CapAcitance"))
    )
    (comp (ref "C15")
      (value "100nF")
      (footprint "easyedapro:C0805")
      (libsource (lib "easyedapro") (part "CapAcitance"))
    )
    (comp (ref "C16")
      (value "10uF")
      (footprint "easyedapro:C0805")
      (libsource (lib "easyedapro") (part "CapAcitance"))
    )
    (comp (ref "C17")
      (value "10uF")
      (footprint "easyedapro:C0805")
      (libsource (lib "easyedapro") (part "CapAcitance"))
    )
    (comp (ref "C33")
      (value "100nF")
      (footprint "easyedapro:C0805")
      (libsource (lib "easyedapro") (part "CapAcitance"))
    )
    (comp (ref "C44")
      (value "10uF")
      (footprint "easyedapro:C0805")
      (libsource (lib "easyedapro") (part "CapAcitance"))
    )
    (comp (ref "C45")
      (value "10uF")
      (footprint "easyedapro:C0805")
      (libsource (lib "easyedapro") (part "CapAcitance"))
    )
    (comp (ref "C46")
      (value "100nF")
      (footprint "easyedapro:C0805")
      (libsource (lib "easyedapro") (part "CapAcitance"))
    )
    (comp (ref "C47")
      (value "100nF")
      (footprint "easyedapro:C0805")
      (libsource (lib "easyedapro") (part "CapAcitance"))
    )
    (comp (ref "C48")
      (value "100nF")
      (footprint "easyedapro:C0805")
      (libsource (lib "easyedapro") (part "CapAcitance"))
    )
    (comp (ref "D1")
      (value "SS34B")
      (footprint "easyedapro:SMB_L4.6-W3.5-LS5.3-RD")
      (fields (field (name "Manufacturer") "宏嘉诚"))
      (libsource (lib "easyedapro") (part "SS34B_C7420366"))
    )
    (comp (ref "DC1")
      (value "DC-005-A200")
      (footprint "easyedapro:DC-IN-TH_DC-005-A200")
      (fields (field (name "Manufacturer") "XUNPU(讯普)"))
      (libsource (lib "easyedapro") (part "DC-005-A200"))
    )
    (comp (ref "L1")
      (value "47uH")
      (footprint "easyedapro:IND-SMD_L10.8-W10.0_SLO1040H")
      (fields
        (field (name "Manufacturer Part") "SLO1040H470MTT")
        (field (name "Manufacturer") "Sunltech(韩国顺磁)")
      )
      (libsource (lib "easyedapro") (part "SLO1040H470MTT"))
    )
    (comp (ref "LED1")
      (value "XL-2012SURC")
      (footprint "easyedapro:LED0805-RD_RED")
      (fields (field (name "Manufacturer") "XINGLIGHT(成兴光)"))
      (libsource (lib "easyedapro") (part "XL-2012SURC"))
    )
    (comp (ref "LED2")
      (value "XL-2012SURC")
      (footprint "easyedapro:LED0805-RD_RED")
      (fields (field (name "Manufacturer") "XINGLIGHT(成兴光)"))
      (libsource (lib "easyedapro") (part "XL-2012SURC"))
    )
    (comp (ref "R5") (value "3.1K") (footprint "easyedapro:R1210") (libsource (lib "easyedapro") (part "电阻")))
    (comp (ref "R6") (value "1K") (footprint "easyedapro:R1210") (libsource (lib "easyedapro") (part "电阻")))
    (comp (ref "R7") (value "300R") (footprint "easyedapro:R1210") (libsource (lib "easyedapro") (part "电阻")))
    (comp (ref "R26")
      (value "300R")
      (footprint "easyedapro:R1210")
      (libsource (lib "easyedapro") (part "电阻"))
    )
    (comp (ref "R27")
      (value "100K")
      (footprint "easyedapro:R1210")
      (libsource (lib "easyedapro") (part "电阻"))
    )
    (comp (ref "R28")
      (value "100K")
      (footprint "easyedapro:R1210")
      (libsource (lib "easyedapro") (part "电阻"))
    )
    (comp (ref "U1")
      (value "AP1501-50K5G-13")
      (footprint "easyedapro:TO-263-5_L10.2-W9.2-P1.70-LS15.2-TL")
      (fields (field (name "Manufacturer") "DIODES(美台)"))
      (libsource (lib "easyedapro") (part "AP1501-50K5G-13"))
    )
    (comp (ref "U2")
      (value "RT9013-33GB")
      (footprint "easyedapro:SOT-23-5_L3.0-W1.7-P0.95-LS2.8-BL")
      (fields (field (name "Manufacturer") "RICHTEK(立锜)"))
      (libsource (lib "easyedapro") (part "RT9013-33GB"))
    )
    (comp (ref "U3")
      (value "RT9013-33GB")
      (footprint "easyedapro:SOT-23-5_L3.0-W1.7-P0.95-LS2.8-BL")
      (fields (field (name "Manufacturer") "RICHTEK(立锜)"))
      (libsource (lib "easyedapro") (part "RT9013-33GB"))
    )
    (comp (ref "U4")
      (value "REF03GSZ-REEL7")
      (footprint "easyedapro:SOIC-8_L4.9-W3.9-P1.27-LS6.0-BL")
      (fields (field (name "Manufacturer") "ADI(亚德诺)"))
      (libsource (lib "easyedapro") (part "REF03GSZ-REEL7"))
    )
    (comp (ref "C18")
      (value "10uF")
      (footprint "easyedapro:CAP-SMD_L3.2-W1.6-RD-C7171")
      (fields (field (name "Manufacturer Part") "TAJA106K016RNJ") (field (name "Manufacturer") "Kyocera AVX"))
      (libsource (lib "easyedapro") (part "TAJA106K016RNJ"))
    )
    (comp (ref "C19")
      (value "10uF")
      (footprint "easyedapro:CAP-SMD_L3.2-W1.6-RD-C7171")
      (fields (field (name "Manufacturer Part") "TAJA106K016RNJ") (field (name "Manufacturer") "Kyocera AVX"))
      (libsource (lib "easyedapro") (part "TAJA106K016RNJ"))
    )
    (comp (ref "C20")
      (value "NF")
      (footprint "easyedapro:C0805")
      (libsource (lib "easyedapro") (part "CapAcitance"))
    )
    (comp (ref "C21")
      (value "NF")
      (footprint "easyedapro:C0805")
      (libsource (lib "easyedapro") (part "CapAcitance"))
    )
    (comp (ref "C22")
      (value "NF")
      (footprint "easyedapro:C0805")
      (libsource (lib "easyedapro") (part "CapAcitance"))
    )
    (comp (ref "C39")
      (value "10uF")
      (footprint "easyedapro:CAP-SMD_L3.2-W1.6-RD-C7171")
      (fields (field (name "Manufacturer Part") "TAJA106K016RNJ") (field (name "Manufacturer") "Kyocera AVX"))
      (libsource (lib "easyedapro") (part "TAJA106K016RNJ"))
    )
    (comp (ref "C40")
      (value "100nF")
      (footprint "easyedapro:C0805")
      (libsource (lib "easyedapro") (part "CapAcitance"))
    )
    (comp (ref "C41")
      (value "10uF")
      (footprint "easyedapro:CAP-SMD_L3.2-W1.6-RD-C7171")
      (fields (field (name "Manufacturer Part") "TAJA106K016RNJ") (field (name "Manufacturer") "Kyocera AVX"))
      (libsource (lib "easyedapro") (part "TAJA106K016RNJ"))
    )
    (comp (ref "CN14")
      (value "DB128V-5.08-3P-GN-S")
      (footprint "easyedapro:CONN-TH_3P-P5.08_DIBO_DB128V-5.08-3P-X")
      (fields (field (name "Manufacturer") "DORABO(地博电气)"))
      (libsource (lib "easyedapro") (part "DB128V-5.08-3P-GN-S"))
    )
    (comp (ref "D2")
      (value "SMAJ5.0CA")
      (footprint "easyedapro:SMA_L4.4-W2.6-LS5.0-BI")
      (fields (field (name "Manufacturer") "Littelfuse(美国力特)"))
      (libsource (lib "easyedapro") (part "SMAJ5.0CA-C83324"))
    )
    (comp (ref "D3")
      (value "SMAJ5.0CA")
      (footprint "easyedapro:SMA_L4.4-W2.6-LS5.0-BI")
      (fields (field (name "Manufacturer") "Littelfuse(美国力特)"))
      (libsource (lib "easyedapro") (part "SMAJ5.0CA-C83324"))
    )
    (comp (ref "D4")
      (value "SMAJ5.0CA")
      (footprint "easyedapro:SMA_L4.4-W2.6-LS5.0-BI")
      (fields (field (name "Manufacturer") "Littelfuse(美国力特)"))
      (libsource (lib "easyedapro") (part "SMAJ5.0CA-C83324"))
    )
    (comp (ref "L4")
      (value "NF")
      (footprint "easyedapro:L0805")
      (libsource (lib "easyedapro") (part "SDFL2012S100KTF"))
    )
    (comp (ref "R9") (value "10K") (footprint "easyedapro:R1210") (libsource (lib "easyedapro") (part "电阻")))
    (comp (ref "R42") (value "1K") (footprint "easyedapro:R1210") (libsource (lib "easyedapro") (part "电阻")))
    (comp (ref "R43") (value "1K") (footprint "easyedapro:R1210") (libsource (lib "easyedapro") (part "电阻")))
    (comp (ref "R44") (value "10R") (footprint "easyedapro:R1210") (libsource (lib "easyedapro") (part "电阻")))
    (comp (ref "R45") (value "10R") (footprint "easyedapro:R1210") (libsource (lib "easyedapro") (part "电阻")))
    (comp (ref "R46") (value "1K") (footprint "easyedapro:R1210") (libsource (lib "easyedapro") (part "电阻")))
    (comp (ref "R47") (value "1K") (footprint "easyedapro:R1210") (libsource (lib "easyedapro") (part "电阻")))
    (comp (ref "RF1")
      (value "BWIPX-1-001E")
      (footprint "easyedapro:IPEX-SMD_BWIPX-1-001E")
      (fields (field (name "Manufacturer") "BAT WIRELESS(蝙蝠无线)"))
      (libsource (lib "easyedapro") (part "BWIPX-1-001E"))
    )
    (comp (ref "U44")
      (value "CA-IS3092W")
      (footprint "easyedapro:SOIC-16_L10.3-W7.5-P1.27-LS10.3-BL")
      (fields (field (name "Manufacturer") "Chipanalog(川土微)"))
      (libsource (lib "easyedapro") (part "CA-IS3092W"))
    )
  )
  (nets
    (net (code "1") (name "+5V") (class "Default")
      (node (ref "C10") (pin "2") (pinfunction "2_2") (pintype "input"))
      (node (ref "C11") (pin "2") (pinfunction "2_2") (pintype "input"))
      (node (ref "C12") (pin "2") (pinfunction "2_2") (pintype "input"))
      (node (ref "C13") (pin "2") (pinfunction "2_2") (pintype "input"))
      (node (ref "C14") (pin "2") (pinfunction "2_2") (pintype "input"))
      (node (ref "C15") (pin "2") (pinfunction "2_2") (pintype "input"))
      (node (ref "C25") (pin "1") (pinfunction "1_1") (pintype "input"))
      (node (ref "C47") (pin "1") (pinfunction "1_1") (pintype "input"))
      (node (ref "C6") (pin "1") (pinfunction "1_1") (pintype "input"))
      (node (ref "C7") (pin "1") (pinfunction "1_1") (pintype "input"))
      (node (ref "FPC1") (pin "9") (pinfunction "9_9") (pintype "unspecified"))
      (node (ref "L1") (pin "1") (pinfunction "1_1") (pintype "unspecified"))
      (node (ref "R27") (pin "1") (pinfunction "1_1") (pintype "input"))
      (node (ref "R5") (pin "2") (pinfunction "2_2") (pintype "input"))
      (node (ref "U2") (pin "1") (pinfunction "VIN_1") (pintype "unspecified"))
      (node (ref "U2") (pin "3") (pinfunction "EN_3") (pintype "unspecified"))
      (node (ref "U29") (pin "1") (pinfunction "VCCA_1") (pintype "unspecified"))
      (node (ref "U3") (pin "1") (pinfunction "VIN_1") (pintype "unspecified"))
      (node (ref "U4") (pin "2") (pinfunction "VIN_2") (pintype "unspecified"))
    )
    (net (code "2") (name "AGND") (class "Default")
      (node (ref "C1") (pin "1") (pinfunction "1_1") (pintype "input"))
      (node (ref "C26") (pin "1") (pinfunction "1_1") (pintype "input"))
      (node (ref "C27") (pin "1") (pinfunction "1_1") (pintype "input"))
      (node (ref "C28") (pin "1") (pinfunction "1_1") (pintype "input"))
      (node (ref "C29") (pin "1") (pinfunction "1_1") (pintype "input"))
      (node (ref "C30") (pin "1") (pinfunction "1_1") (pintype "input"))
      (node (ref "C31") (pin "1") (pinfunction "1_1") (pintype "input"))
      (node (ref "C32") (pin "1") (pinfunction "1_1") (pintype "input"))
      (node (ref "C34") (pin "1") (pinfunction "1_1") (pintype "input"))
      (node (ref "C35") (pin "1") (pinfunction "1_1") (pintype "input"))
      (node (ref "C36") (pin "1") (pinfunction "1_1") (pintype "input"))
      (node (ref "C37") (pin "1") (pinfunction "1_1") (pintype "input"))
      (node (ref "C38") (pin "1") (pinfunction "1_1") (pintype "input"))
      (node (ref "C48") (pin "1") (pinfunction "1_1") (pintype "input"))
      (node (ref "CN13") (pin "1") (pinfunction "1_1") (pintype "unspecified"))
      (node (ref "R15") (pin "2") (pinfunction "2_2") (pintype "input"))
      (node (ref "R17") (pin "2") (pinfunction "2_2") (pintype "input"))
      (node (ref "R21") (pin "2") (pinfunction "2_2") (pintype "input"))
      (node (ref "R23") (pin "2") (pinfunction "2_2") (pintype "input"))
      (node (ref "R8") (pin "1") (pinfunction "1_1") (pintype "input"))
      (node (ref "U20") (pin "19") (pinfunction "VSSA_19") (pintype "unspecified"))
      (node (ref "U20") (pin "20") (pinfunction "VREF-_20") (pintype "unspecified"))
      (node (ref "U31") (pin "1") (pinfunction "1_1") (pintype "unspecified"))
      (node (ref "U32") (pin "1") (pinfunction "1_1") (pintype "unspecified"))
      (node (ref "U33") (pin "4") (pinfunction "VSS_4") (pintype "unspecified"))
      (node (ref "U34") (pin "1") (pinfunction "1_1") (pintype "unspecified"))
      (node (ref "U35") (pin "1") (pinfunction "1_1") (pintype "unspecified"))
      (node (ref "U36") (pin "4") (pinfunction "VSS_4") (pintype "unspecified"))
      (node (ref "U37") (pin "1") (pinfunction "1_1") (pintype "unspecified"))
      (node (ref "U39") (pin "4") (pinfunction "VSS_4") (pintype "unspecified"))
      (node (ref "U40") (pin "1") (pinfunction "1_1") (pintype "unspecified"))
      (node (ref "U41") (pin "1") (pinfunction "1_1") (pintype "unspecified"))
      (node (ref "U42") (pin "1") (pinfunction "1_1") (pintype "unspecified"))
      (node (ref "U43") (pin "4") (pinfunction "VSS_4") (pintype "unspecified"))
    )
    (net (code "3") (name "AIN1") (class "Default")
      (node (ref "R18") (pin "2") (pinfunction "2_2") (pintype "input"))
      (node (ref "U20") (pin "23") (pinfunction "PA0-WKUP_23") (pintype "bidirectional"))
    )
    (net (code "4") (name "AIN2") (class "Default")
      (node (ref "R19") (pin "2") (pinfunction "2_2") (pintype "input"))
      (node (ref "U20") (pin "24") (pinfunction "PA1_24") (pintype "bidirectional"))
    )
    (net (code "5") (name "AIN3") (class "Default")
      (node (ref "R24") (pin "2") (pinfunction "2_2") (pintype "input"))
      (node (ref "U20") (pin "25") (pinfunction "PA2_25") (pintype "bidirectional"))
    )
    (net (code "6") (name "AIN4") (class "Default")
      (node (ref "R25") (pin "2") (pinfunction "2_2") (pintype "input"))
      (node (ref "U20") (pin "26") (pinfunction "PA3_26") (pintype "bidirectional"))
    )
    (net (code "7") (name "AIN5") (class "Default")
      (node (ref "R30") (pin "2") (pinfunction "2_2") (pintype "input"))
      (node (ref "U20") (pin "29") (pinfunction "PA4_29") (pintype "bidirectional"))
    )
    (net (code "8") (name "AIN6") (class "Default")
      (node (ref "R31") (pin "2") (pinfunction "2_2") (pintype "input"))
      (node (ref "U20") (pin "30") (pinfunction "PA5_30") (pintype "bidirectional"))
    )
    (net (code "9") (name "AIN7") (class "Default")
      (node (ref "R36") (pin "2") (pinfunction "2_2") (pintype "input"))
      (node (ref "U20") (pin "31") (pinfunction "PA6_31") (pintype "bidirectional"))
    )
    (net (code "10") (name "AIN8") (class "Default")
      (node (ref "R39") (pin "2") (pinfunction "2_2") (pintype "input"))
      (node (ref "U20") (pin "32") (pinfunction "PA7_32") (pintype "bidirectional"))
    )
    (net (code "11") (name "AVDD") (class "Default")
      (node (ref "C1") (pin "2") (pinfunction "2_2") (pintype "input"))
      (node (ref "C28") (pin "2") (pinfunction "2_2") (pintype "input"))
      (node (ref "C31") (pin "2") (pinfunction "2_2") (pintype "input"))
      (node (ref "C34") (pin "2") (pinfunction "2_2") (pintype "input"))
      (node (ref "C37") (pin "2") (pinfunction "2_2") (pintype "input"))
      (node (ref "L2") (pin "2") (pinfunction "2_2") (pintype "unspecified"))
      (node (ref "U20") (pin "22") (pinfunction "VDDA_22") (pintype "unspecified"))
      (node (ref "U33") (pin "8") (pinfunction "VDD_8") (pintype "unspecified"))
      (node (ref "U36") (pin "8") (pinfunction "VDD_8") (pintype "unspecified"))
      (node (ref "U39") (pin "8") (pinfunction "VDD_8") (pintype "unspecified"))
      (node (ref "U43") (pin "8") (pinfunction "VDD_8") (pintype "unspecified"))
    )
    (net (code "12") (name "DC") (class "Default")
      (node (ref "C8") (pin "1") (pinfunction "1_1") (pintype "input"))
      (node (ref "C9") (pin "1") (pinfunction "1_1") (pintype "input"))
      (node (ref "DC1") (pin "1") (pinfunction "1_1") (pintype "unspecified"))
      (node (ref "U1") (pin "1") (pinfunction "VIN_1") (pintype "unspecified"))
    )
    (net (code "13") (name "FLASH_SPI_CS") (class "Default")
      (node (ref "R4") (pin "2") (pinfunction "2_2") (pintype "input"))
      (node (ref "U19") (pin "1") (pinfunction "CS#_1") (pintype "unspecified"))
      (node (ref "U20") (pin "51") (pinfunction "PB12_51") (pintype "bidirectional"))
    )
    (net (code "14") (name "GND") (class "Default")
      (node (ref "C10") (pin "1") (pinfunction "1_1") (pintype "input"))
      (node (ref "C11") (pin "1") (pinfunction "1_1") (pintype "input"))
      (node (ref "C12") (pin "1") (pinfunction "1_1") (pintype "input"))
      (node (ref "C13") (pin "1") (pinfunction "1_1") (pintype "input"))
      (node (ref "C14") (pin "1") (pinfunction "1_1") (pintype "input"))
      (node (ref "C15") (pin "1") (pinfunction "1_1") (pintype "input"))
      (node (ref "C16") (pin "1") (pinfunction "1_1") (pintype "input"))
      (node (ref "C17") (pin "1") (pinfunction "1_1") (pintype "input"))
      (node (ref "C2") (pin "1") (pinfunction "1_1") (pintype "input"))
      (node (ref "C20") (pin "1") (pinfunction "1_1") (pintype "input"))
      (node (ref "C21") (pin "1") (pinfunction "1_1") (pintype "input"))
      (node (ref "C23") (pin "1") (pinfunction "1_1") (pintype "input"))
      (node (ref "C24") (pin "2") (pinfunction "2_2") (pintype "input"))
      (node (ref "C25") (pin "2") (pinfunction "2_2") (pintype "input"))
      (node (ref "C3") (pin "1") (pinfunction "1_1") (pintype "input"))
      (node (ref "C33") (pin "1") (pinfunction "1_1") (pintype "input"))
      (node (ref "C4") (pin "1") (pinfunction "1_1") (pintype "input"))
      (node (ref "C42") (pin "1") (pinfunction "1_1") (pintype "input"))
      (node (ref "C43") (pin "1") (pinfunction "1_1") (pintype "input"))
      (node (ref "C44") (pin "1") (pinfunction "1_1") (pintype "input"))
      (node (ref "C45") (pin "1") (pinfunction "1_1") (pintype "input"))
      (node (ref "C46") (pin "1") (pinfunction "1_1") (pintype "input"))
      (node (ref "C47") (pin "2") (pinfunction "2_2") (pintype "input"))
      (node (ref "C49") (pin "2") (pinfunction "2_2") (pintype "input"))
      (node (ref "C5") (pin "1") (pinfunction "1_1") (pintype "input"))
      (node (ref "C50") (pin "2") (pinfunction "2_2") (pintype "input"))
      (node (ref "C51") (pin "2") (pinfunction "2_2") (pintype "input"))
      (node (ref "C52") (pin "1") (pinfunction "1_1") (pintype "input"))
      (node (ref "C53") (pin "1") (pinfunction "1_1") (pintype "input"))
      (node (ref "C54") (pin "1") (pinfunction "1_1") (pintype "input"))
      (node (ref "C55") (pin "1") (pinfunction "1_1") (pintype "input"))
      (node (ref "C56") (pin "1") (pinfunction "1_1") (pintype "input"))
      (node (ref "C6") (pin "2") (pinfunction "2_2") (pintype "input"))
      (node (ref "C7") (pin "2") (pinfunction "2_2") (pintype "input"))
      (node (ref "C8") (pin "2") (pinfunction "2_2") (pintype "input"))
      (node (ref "C9") (pin "2") (pinfunction "2_2") (pintype "input"))
      (node (ref "D1") (pin "2") (pinfunction "A_2") (pintype "unspecified"))
      (node (ref "DC1") (pin "2") (pinfunction "2_2") (pintype "unspecified"))
      (node (ref "DC1") (pin "3") (pinfunction "3_3") (pintype "unspecified"))
      (node (ref "FPC1") (pin "10") (pinfunction "10_10") (pintype "unspecified"))
      (node (ref "FPC1") (pin "11") (pinfunction "11_11") (pintype "unspecified"))
      (node (ref "FPC1") (pin "12") (pinfunction "12_12") (pintype "unspecified"))
      (node (ref "FPC3") (pin "6") (pinfunction "6_6") (pintype "unspecified"))
      (node (ref "FPC3") (pin "7") (pinfunction "7_7") (pintype "unspecified"))
      (node (ref "FPC3") (pin "8") (pinfunction "8_8") (pintype "unspecified"))
      (node (ref "H1") (pin "4") (pinfunction "4_4") (pintype "unspecified"))
      (node (ref "LED1") (pin "1") (pinfunction "K_1") (pintype "unspecified"))
      (node (ref "LED2") (pin "1") (pinfunction "K_1") (pintype "unspecified"))
      (node (ref "P1") (pin "8") (pinfunction "8_8") (pintype "unspecified"))
      (node (ref "R10") (pin "1") (pinfunction "1_1") (pintype "input"))
      (node (ref "R27") (pin "2") (pinfunction "2_2") (pintype "input"))
      (node (ref "R28") (pin "2") (pinfunction "2_2") (pintype "input"))
      (node (ref "R6") (pin "1") (pinfunction "1_1") (pintype "input"))
      (node (ref "R8") (pin "2") (pinfunction "2_2") (pintype "input"))
      (node (ref "R9") (pin "2") (pinfunction "2_2") (pintype "input"))
      (node (ref "SCREW1") (pin "1") (pinfunction "1_1") (pintype "input"))
      (node (ref "SCREW2") (pin "1") (pinfunction "1_1") (pintype "input"))
      (node (ref "SCREW3") (pin "1") (pinfunction "1_1") (pintype "input"))
      (node (ref "SCREW4") (pin "1") (pinfunction "1_1") (pintype "input"))
      (node (ref "SCREW5") (pin "1") (pinfunction "1_1") (pintype "input"))
      (node (ref "SCREW6") (pin "1") (pinfunction "1_1") (pintype "input"))
      (node (ref "U1") (pin "3") (pinfunction "GND_3") (pintype "unspecified"))
      (node (ref "U1") (pin "5") (pinfunction "SD_5") (pintype "unspecified"))
      (node (ref "U1") (pin "6") (pinfunction "GND_6") (pintype "unspecified"))
      (node (ref "U19") (pin "4") (pinfunction "GND_4") (pintype "unspecified"))
      (node (ref "U2") (pin "2") (pinfunction "GND_2") (pintype "unspecified"))
      (node (ref "U20") (pin "10") (pinfunction "VSS_5_10") (pintype "unspecified"))
      (node (ref "U20") (pin "27") (pinfunction "VSS_4_27") (pintype "unspecified"))
      (node (ref "U20") (pin "49") (pinfunction "VSS_1_49") (pintype "unspecified"))
      (node (ref "U20") (pin "74") (pinfunction "VSS_2_74") (pintype "unspecified"))
      (node (ref "U20") (pin "99") (pinfunction "VSS_3_99") (pintype "unspecified"))
      (node (ref "U22") (pin "25") (pinfunction "GND_25") (pintype "unspecified"))
      (node (ref "U22") (pin "9") (pinfunction "GND_9") (pintype "unspecified"))
      (node (ref "U29") (pin "11") (pinfunction "GND_11") (pintype "unspecified"))
      (node (ref "U29") (pin "12") (pinfunction "GND_12") (pintype "unspecified"))
      (node (ref "U29") (pin "13") (pinfunction "GND_13") (pintype "unspecified"))
      (node (ref "U3") (pin "2") (pinfunction "GND_2") (pintype "unspecified"))
      (node (ref "U4") (pin "4") (pinfunction "GND_4") (pintype "unspecified"))
    )
    (net (code "16") (name "I1+") (class "Default")
      (node (ref "CN5") (pin "1") (pinfunction "1_1") (pintype "unspecified"))
      (node (ref "R32") (pin "2") (pinfunction "2_2") (pintype "input"))
    )
    (net (code "17") (name "I1-") (class "Default")
      (node (ref "CN6") (pin "1") (pinfunction "1_1") (pintype "unspecified"))
      (node (ref "R32") (pin "1") (pinfunction "1_1") (pintype "input"))
      (node (ref "R33") (pin "1") (pinfunction "1_1") (pintype "input"))
    )
    (net (code "18") (name "I2+") (class "Default")
      (node (ref "CN7") (pin "1") (pinfunction "1_1") (pintype "unspecified"))
      (node (ref "R34") (pin "2") (pinfunction "2_2") (pintype "input"))
    )
    (net (code "19") (name "I2-") (class "Default")
      (node (ref "CN8") (pin "1") (pinfunction "1_1") (pintype "unspecified"))
      (node (ref "R34") (pin "1") (pinfunction "1_1") (pintype "input"))
      (node (ref "R35") (pin "1") (pinfunction "1_1") (pintype "input"))
    )
    (net (code "20") (name "I3+") (class "Default")
      (node (ref "CN9") (pin "1") (pinfunction "1_1") (pintype "unspecified"))
      (node (ref "R37") (pin "2") (pinfunction "2_2") (pintype "input"))
    )
    (net (code "21") (name "I3-") (class "Default")
      (node (ref "CN10") (pin "1") (pinfunction "1_1") (pintype "unspecified"))
      (node (ref "R37") (pin "1") (pinfunction "1_1") (pintype "input"))
      (node (ref "R38") (pin "1") (pinfunction "1_1") (pintype "input"))
    )
    (net (code "22") (name "I4+") (class "Default")
      (node (ref "CN11") (pin "1") (pinfunction "1_1") (pintype "unspecified"))
      (node (ref "R40") (pin "2") (pinfunction "2_2") (pintype "input"))
    )
    (net (code "23") (name "I4-") (class "Default")
      (node (ref "CN12") (pin "1") (pinfunction "1_1") (pintype "unspecified"))
      (node (ref "R40") (pin "1") (pinfunction "1_1") (pintype "input"))
      (node (ref "R41") (pin "1") (pinfunction "1_1") (pintype "input"))
    )
    (net (code "24") (name "Net-(D1-K)") (class "Default")
      (node (ref "D1") (pin "1") (pinfunction "K_1") (pintype "unspecified"))
      (node (ref "L1") (pin "2") (pinfunction "2_2") (pintype "unspecified"))
      (node (ref "U1") (pin "2") (pinfunction "OUTPUT_2") (pintype "unspecified"))
    )
    (net (code "25") (name "Net-(FPC1-Pad1)") (class "Default")
      (node (ref "FPC1") (pin "1") (pinfunction "1_1") (pintype "unspecified"))
      (node (ref "R55") (pin "1") (pinfunction "1_1") (pintype "input"))
    )
    (net (code "26") (name "Net-(FPC1-Pad2)") (class "Default")
      (node (ref "FPC1") (pin "2") (pinfunction "2_2") (pintype "unspecified"))
      (node (ref "R56") (pin "1") (pinfunction "1_1") (pintype "input"))
    )
    (net (code "27") (name "Net-(FPC1-Pad3)") (class "Default")
      (node (ref "FPC1") (pin "3") (pinfunction "3_3") (pintype "unspecified"))
      (node (ref "R57") (pin "1") (pinfunction "1_1") (pintype "input"))
    )
    (net (code "28") (name "Net-(FPC1-Pad4)") (class "Default")
      (node (ref "FPC1") (pin "4") (pinfunction "4_4") (pintype "unspecified"))
      (node (ref "R58") (pin "1") (pinfunction "1_1") (pintype "input"))
    )
    (net (code "29") (name "Net-(FPC1-Pad5)") (class "Default")
      (node (ref "FPC1") (pin "5") (pinfunction "5_5") (pintype "unspecified"))
      (node (ref "R59") (pin "1") (pinfunction "1_1") (pintype "input"))
    )
    (net (code "30") (name "Net-(FPC1-Pad6)") (class "Default")
      (node (ref "FPC1") (pin "6") (pinfunction "6_6") (pintype "unspecified"))
      (node (ref "R60") (pin "1") (pinfunction "1_1") (pintype "input"))
    )
    (net (code "31") (name "Net-(FPC1-Pad7)") (class "Default")
      (node (ref "FPC1") (pin "7") (pinfunction "7_7") (pintype "unspecified"))
      (node (ref "R61") (pin "1") (pinfunction "1_1") (pintype "input"))
    )
    (net (code "32") (name "Net-(FPC1-Pad8)") (class "Default")
      (node (ref "FPC1") (pin "8") (pinfunction "8_8") (pintype "unspecified"))
      (node (ref "R62") (pin "1") (pinfunction "1_1") (pintype "input"))
    )
    (net (code "33") (name "Net-(H1-Pad2)") (class "Default")
      (node (ref "H1") (pin "2") (pinfunction "2_2") (pintype "unspecified"))
      (node (ref "R12") (pin "2") (pinfunction "2_2") (pintype "input"))
    )
    (net (code "34") (name "Net-(H1-Pad3)") (class "Default")
      (node (ref "H1") (pin "3") (pinfunction "3_3") (pintype "unspecified"))
      (node (ref "R13") (pin "2") (pinfunction "2_2") (pintype "input"))
    )
    (net (code "35") (name "Net-(LED1-A)") (class "Default")
      (node (ref "LED1") (pin "2") (pinfunction "A_2") (pintype "unspecified"))
      (node (ref "R26") (pin "1") (pinfunction "1_1") (pintype "input"))
    )
    (net (code "36") (name "Net-(LED2-A)") (class "Default")
      (node (ref "LED2") (pin "2") (pinfunction "A_2") (pintype "unspecified"))
      (node (ref "R7") (pin "1") (pinfunction "1_1") (pintype "input"))
    )
    (net (code "37") (name "Net-(P1-Pad2)") (class "Default")
      (node (ref "P1") (pin "2") (pinfunction "2_2") (pintype "unspecified"))
      (node (ref "R49") (pin "1") (pinfunction "1_1") (pintype "input"))
    )
    (net (code "38") (name "Net-(P1-Pad3)") (class "Default")
      (node (ref "P1") (pin "3") (pinfunction "3_3") (pintype "unspecified"))
      (node (ref "R50") (pin "1") (pinfunction "1_1") (pintype "input"))
    )
    (net (code "39") (name "Net-(P1-Pad4)") (class "Default")
      (node (ref "P1") (pin "4") (pinfunction "4_4") (pintype "unspecified"))
      (node (ref "R51") (pin "1") (pinfunction "1_1") (pintype "input"))
    )
    (net (code "40") (name "Net-(P1-Pad5)") (class "Default")
      (node (ref "P1") (pin "5") (pinfunction "5_5") (pintype "unspecified"))
      (node (ref "R52") (pin "1") (pinfunction "1_1") (pintype "input"))
    )
    (net (code "41") (name "Net-(P1-Pad6)") (class "Default")
      (node (ref "P1") (pin "6") (pinfunction "6_6") (pintype "unspecified"))
      (node (ref "R53") (pin "1") (pinfunction "1_1") (pintype "input"))
    )
    (net (code "42") (name "Net-(P1-Pad7)") (class "Default")
      (node (ref "P1") (pin "7") (pinfunction "7_7") (pintype "unspecified"))
      (node (ref "R54") (pin "1") (pinfunction "1_1") (pintype "input"))
    )
    (net (code "43") (name "Net-(R1-Pad1)") (class "Default")
      (node (ref "R1") (pin "1") (pinfunction "1_1") (pintype "input"))
      (node (ref "U22") (pin "24") (pinfunction "VDD_24") (pintype "unspecified"))
    )
    (net (code "44") (name "Net-(U1-FB)") (class "Default")
      (node (ref "R5") (pin "1") (pinfunction "1_1") (pintype "input"))
      (node (ref "R6") (pin "2") (pinfunction "2_2") (pintype "input"))
      (node (ref "U1") (pin "4") (pinfunction "FB_4") (pintype "unspecified"))
    )
    (net (code "45") (name "Net-(U19-IO2)") (class "Default")
      (node (ref "R3") (pin "1") (pinfunction "1_1") (pintype "input"))
      (node (ref "U19") (pin "3") (pinfunction "IO2_3") (pintype "unspecified"))
    )
    (net (code "46") (name "Net-(U20A-BOOT0)") (class "Default")
      (node (ref "R10") (pin "2") (pinfunction "2_2") (pintype "input"))
      (node (ref "U20") (pin "94") (pinfunction "BOOT0_94") (pintype "unspecified"))
    )
    (net (code "47") (name "Net-(U20A-NRST)") (class "Default")
      (node (ref "C23") (pin "2") (pinfunction "2_2") (pintype "input"))
      (node (ref "R11") (pin "2") (pinfunction "2_2") (pintype "input"))
      (node (ref "U20") (pin "14") (pinfunction "NRST_14") (pintype "bidirectional"))
    )
    (net (code "48") (name "Net-(U20A-OSC_IN)") (class "Default")
      (node (ref "C42") (pin "2") (pinfunction "2_2") (pintype "input"))
      (node (ref "R48") (pin "1") (pinfunction "1_1") (pintype "input"))
      (node (ref "U20") (pin "12") (pinfunction "OSC_IN_12") (pintype "unspecified"))
      (node (ref "X1") (pin "1") (pinfunction "OSC1_1") (pintype "input"))
    )
    (net (code "49") (name "Net-(U20A-OSC_OUT)") (class "Default")
      (node (ref "C43") (pin "2") (pinfunction "2_2") (pintype "input"))
      (node (ref "R48") (pin "2") (pinfunction "2_2") (pintype "input"))
      (node (ref "U20") (pin "13") (pinfunction "OSC_OUT_13") (pintype "unspecified"))
      (node (ref "X1") (pin "2") (pinfunction "OSC2_2") (pintype "input"))
    )
    (net (code "50") (name "Net-(U20A-PA13)") (class "Default")
      (node (ref "R12") (pin "1") (pinfunction "1_1") (pintype "input"))
      (node (ref "U20") (pin "72") (pinfunction "PA13_72") (pintype "bidirectional"))
    )
    (net (code "51") (name "Net-(U20A-PA14)") (class "Default")
      (node (ref "R13") (pin "1") (pinfunction "1_1") (pintype "input"))
      (node (ref "U20") (pin "76") (pinfunction "PA14_76") (pintype "bidirectional"))
    )
    (net (code "52") (name "Net-(U20A-PB10)") (class "Default")
      (node (ref "R49") (pin "2") (pinfunction "2_2") (pintype "input"))
      (node (ref "U20") (pin "47") (pinfunction "PB10_47") (pintype "bidirectional"))
    )
    (net (code "53") (name "Net-(U20A-PB11)") (class "Default")
      (node (ref "R50") (pin "2") (pinfunction "2_2") (pintype "input"))
      (node (ref "U20") (pin "48") (pinfunction "PB11_48") (pintype "bidirectional"))
    )
    (net (code "54") (name "Net-(U20A-PC3)") (class "Default")
      (node (ref "FPC3") (pin "1") (pinfunction "1_1") (pintype "unspecified"))
      (node (ref "R63") (pin "1") (pinfunction "1_1") (pintype "input"))
      (node (ref "U20") (pin "18") (pinfunction "PC3_18") (pintype "bidirectional"))
    )
    (net (code "55") (name "Net-(U20A-PC4)") (class "Default")
      (node (ref "FPC3") (pin "2") (pinfunction "2_2") (pintype "unspecified"))
      (node (ref "R64") (pin "1") (pinfunction "1_1") (pintype "input"))
      (node (ref "U20") (pin "33") (pinfunction "PC4_33") (pintype "bidirectional"))
    )
    (net (code "56") (name "Net-(U20A-PC5)") (class "Default")
      (node (ref "FPC3") (pin "3") (pinfunction "3_3") (pintype "unspecified"))
      (node (ref "R65") (pin "1") (pinfunction "1_1") (pintype "input"))
      (node (ref "U20") (pin "34") (pinfunction "PC5_34") (pintype "bidirectional"))
    )
    (net (code "57") (name "Net-(U20A-PC6)") (class "Default")
      (node (ref "FPC3") (pin "4") (pinfunction "4_4") (pintype "unspecified"))
      (node (ref "R66") (pin "1") (pinfunction "1_1") (pintype "input"))
      (node (ref "U20") (pin "63") (pinfunction "PC6_63") (pintype "bidirectional"))
    )
    (net (code "58") (name "Net-(U20A-PC7)") (class "Default")
      (node (ref "FPC3") (pin "5") (pinfunction "5_5") (pintype "unspecified"))
      (node (ref "R67") (pin "1") (pinfunction "1_1") (pintype "input"))
      (node (ref "U20") (pin "64") (pinfunction "PC7_64") (pintype "bidirectional"))
    )
    (net (code "59") (name "Net-(U20A-PC14-OSC32_IN)") (class "Default")
      (node (ref "C50") (pin "1") (pinfunction "1_1") (pintype "input"))
      (node (ref "U20") (pin "8") (pinfunction "PC14-OSC32_IN_8") (pintype "bidirectional"))
      (node (ref "X2") (pin "2") (pinfunction "OSC2_2") (pintype "input"))
    )
    (net (code "60") (name "Net-(U20A-PC15-OSC32_OUT)") (class "Default")
      (node (ref "C51") (pin "1") (pinfunction "1_1") (pintype "input"))
      (node (ref "U20") (pin "9") (pinfunction "PC15-OSC32_OUT_9") (pintype "bidirectional"))
      (node (ref "X2") (pin "1") (pinfunction "OSC1_1") (pintype "input"))
    )
    (net (code "61") (name "Net-(U29-A1)") (class "Default")
      (node (ref "R55") (pin "2") (pinfunction "2_2") (pintype "input"))
      (node (ref "U29") (pin "3") (pinfunction "A1_3") (pintype "unspecified"))
    )
    (net (code "62") (name "Net-(U29-A2)") (class "Default")
      (node (ref "R56") (pin "2") (pinfunction "2_2") (pintype "input"))
      (node (ref "U29") (pin "4") (pinfunction "A2_4") (pintype "unspecified"))
    )
    (net (code "63") (name "Net-(U29-A3)") (class "Default")
      (node (ref "R57") (pin "2") (pinfunction "2_2") (pintype "input"))
      (node (ref "U29") (pin "5") (pinfunction "A3_5") (pintype "unspecified"))
    )
    (net (code "64") (name "Net-(U29-A4)") (class "Default")
      (node (ref "R58") (pin "2") (pinfunction "2_2") (pintype "input"))
      (node (ref "U29") (pin "6") (pinfunction "A4_6") (pintype "unspecified"))
    )
    (net (code "65") (name "Net-(U29-A5)") (class "Default")
      (node (ref "R59") (pin "2") (pinfunction "2_2") (pintype "input"))
      (node (ref "U29") (pin "7") (pinfunction "A5_7") (pintype "unspecified"))
    )
    (net (code "66") (name "Net-(U29-A6)") (class "Default")
      (node (ref "R60") (pin "2") (pinfunction "2_2") (pintype "input"))
      (node (ref "U29") (pin "8") (pinfunction "A6_8") (pintype "unspecified"))
    )
    (net (code "67") (name "Net-(U29-A7)") (class "Default")
      (node (ref "R61") (pin "2") (pinfunction "2_2") (pintype "input"))
      (node (ref "U29") (pin "9") (pinfunction "A7_9") (pintype "unspecified"))
    )
    (net (code "68") (name "Net-(U29-A8)") (class "Default")
      (node (ref "R62") (pin "2") (pinfunction "2_2") (pintype "input"))
      (node (ref "U29") (pin "10") (pinfunction "A8_10") (pintype "unspecified"))
    )
    (net (code "69") (name "Net-(U33A-IN_A+)") (class "Default")
      (node (ref "C26") (pin "2") (pinfunction "2_2") (pintype "input"))
      (node (ref "R14") (pin "2") (pinfunction "2_2") (pintype "input"))
      (node (ref "R15") (pin "1") (pinfunction "1_1") (pintype "input"))
      (node (ref "U31") (pin "2") (pinfunction "2_2") (pintype "unspecified"))
      (node (ref "U33") (pin "3") (pinfunction "IN_A+_3") (pintype "unspecified"))
    )
    (net (code "70") (name "Net-(U33A-IN_A-)") (class "Default")
      (node (ref "R18") (pin "1") (pinfunction "1_1") (pintype "input"))
      (node (ref "U33") (pin "1") (pinfunction "OUT_A_1") (pintype "output"))
      (node (ref "U33") (pin "2") (pinfunction "IN_A-_2") (pintype "unspecified"))
    )
    (net (code "71") (name "Net-(U33B-IN_B+)") (class "Default")
      (node (ref "C27") (pin "2") (pinfunction "2_2") (pintype "input"))
      (node (ref "R16") (pin "2") (pinfunction "2_2") (pintype "input"))
      (node (ref "R17") (pin "1") (pinfunction "1_1") (pintype "input"))
      (node (ref "U32") (pin "2") (pinfunction "2_2") (pintype "unspecified"))
      (node (ref "U33") (pin "5") (pinfunction "IN_B+_5") (pintype "unspecified"))
    )
    (net (code "72") (name "Net-(U33B-IN_B-)") (class "Default")
      (node (ref "R19") (pin "1") (pinfunction "1_1") (pintype "input"))
      (node (ref "U33") (pin "6") (pinfunction "IN_B-_6") (pintype "unspecified"))
      (node (ref "U33") (pin "7") (pinfunction "OUT_B_7") (pintype "output"))
    )
    (net (code "73") (name "Net-(U36A-IN_A+)") (class "Default")
      (node (ref "C29") (pin "2") (pinfunction "2_2") (pintype "input"))
      (node (ref "R20") (pin "2") (pinfunction "2_2") (pintype "input"))
      (node (ref "R21") (pin "1") (pinfunction "1_1") (pintype "input"))
      (node (ref "U34") (pin "2") (pinfunction "2_2") (pintype "unspecified"))
      (node (ref "U36") (pin "3") (pinfunction "IN_A+_3") (pintype "unspecified"))
    )
    (net (code "74") (name "Net-(U36A-IN_A-)") (class "Default")
      (node (ref "R24") (pin "1") (pinfunction "1_1") (pintype "input"))
      (node (ref "U36") (pin "1") (pinfunction "OUT_A_1") (pintype "output"))
      (node (ref "U36") (pin "2") (pinfunction "IN_A-_2") (pintype "unspecified"))
    )
    (net (code "75") (name "Net-(U36B-IN_B+)") (class "Default")
      (node (ref "C30") (pin "2") (pinfunction "2_2") (pintype "input"))
      (node (ref "R22") (pin "2") (pinfunction "2_2") (pintype "input"))
      (node (ref "R23") (pin "1") (pinfunction "1_1") (pintype "input"))
      (node (ref "U35") (pin "2") (pinfunction "2_2") (pintype "unspecified"))
      (node (ref "U36") (pin "5") (pinfunction "IN_B+_5") (pintype "unspecified"))
    )
    (net (code "76") (name "Net-(U36B-IN_B-)") (class "Default")
      (node (ref "R25") (pin "1") (pinfunction "1_1") (pintype "input"))
      (node (ref "U36") (pin "6") (pinfunction "IN_B-_6") (pintype "unspecified"))
      (node (ref "U36") (pin "7") (pinfunction "OUT_B_7") (pintype "output"))
    )
    (net (code "77") (name "Net-(U39A-IN_A+)") (class "Default")
      (node (ref "C32") (pin "2") (pinfunction "2_2") (pintype "input"))
      (node (ref "R33") (pin "2") (pinfunction "2_2") (pintype "input"))
      (node (ref "U37") (pin "2") (pinfunction "2_2") (pintype "unspecified"))
      (node (ref "U39") (pin "3") (pinfunction "IN_A+_3") (pintype "unspecified"))
    )
    (net (code "78") (name "Net-(U39A-IN_A-)") (class "Default")
      (node (ref "R30") (pin "1") (pinfunction "1_1") (pintype "input"))
      (node (ref "U39") (pin "1") (pinfunction "OUT_A_1") (pintype "output"))
      (node (ref "U39") (pin "2") (pinfunction "IN_A-_2") (pintype "unspecified"))
    )
    (net (code "79") (name "Net-(U39B-IN_B+)") (class "Default")
      (node (ref "C35") (pin "2") (pinfunction "2_2") (pintype "input"))
      (node (ref "R35") (pin "2") (pinfunction "2_2") (pintype "input"))
      (node (ref "U39") (pin "5") (pinfunction "IN_B+_5") (pintype "unspecified"))
      (node (ref "U40") (pin "2") (pinfunction "2_2") (pintype "unspecified"))
    )
    (net (code "80") (name "Net-(U39B-IN_B-)") (class "Default")
      (node (ref "R31") (pin "1") (pinfunction "1_1") (pintype "input"))
      (node (ref "U39") (pin "6") (pinfunction "IN_B-_6") (pintype "unspecified"))
      (node (ref "U39") (pin "7") (pinfunction "OUT_B_7") (pintype "output"))
    )
    (net (code "81") (name "Net-(U43A-IN_A+)") (class "Default")
      (node (ref "C36") (pin "2") (pinfunction "2_2") (pintype "input"))
      (node (ref "R38") (pin "2") (pinfunction "2_2") (pintype "input"))
      (node (ref "U41") (pin "2") (pinfunction "2_2") (pintype "unspecified"))
      (node (ref "U43") (pin "3") (pinfunction "IN_A+_3") (pintype "unspecified"))
    )
    (net (code "82") (name "Net-(U43A-IN_A-)") (class "Default")
      (node (ref "R36") (pin "1") (pinfunction "1_1") (pintype "input"))
      (node (ref "U43") (pin "1") (pinfunction "OUT_A_1") (pintype "output"))
      (node (ref "U43") (pin "2") (pinfunction "IN_A-_2") (pintype "unspecified"))
    )
    (net (code "83") (name "Net-(U43B-IN_B+)") (class "Default")
      (node (ref "C38") (pin "2") (pinfunction "2_2") (pintype "input"))
      (node (ref "R41") (pin "2") (pinfunction "2_2") (pintype "input"))
      (node (ref "U42") (pin "2") (pinfunction "2_2") (pintype "unspecified"))
      (node (ref "U43") (pin "5") (pinfunction "IN_B+_5") (pintype "unspecified"))
    )
    (net (code "84") (name "Net-(U43B-IN_B-)") (class "Default")
      (node (ref "R39") (pin "1") (pinfunction "1_1") (pintype "input"))
      (node (ref "U43") (pin "6") (pinfunction "IN_B-_6") (pintype "unspecified"))
      (node (ref "U43") (pin "7") (pinfunction "OUT_B_7") (pintype "output"))
    )
    (net (code "85") (name "PB0") (class "Default")
      (node (ref "U20") (pin "35") (pinfunction "PB0_35") (pintype "bidirectional"))
      (node (ref "U29") (pin "21") (pinfunction "B1_21") (pintype "unspecified"))
    )
    (net (code "86") (name "PB1") (class "Default")
      (node (ref "U20") (pin "36") (pinfunction "PB1_36") (pintype "bidirectional"))
      (node (ref "U29") (pin "20") (pinfunction "B2_20") (pintype "unspecified"))
    )
    (net (code "87") (name "PB2") (class "Default")
      (node (ref "U20") (pin "37") (pinfunction "PB2_37") (pintype "bidirectional"))
      (node (ref "U29") (pin "19") (pinfunction "B3_19") (pintype "unspecified"))
    )
    (net (code "88") (name "PB3") (class "Default")
      (node (ref "U20") (pin "89") (pinfunction "PB3_89") (pintype "bidirectional"))
      (node (ref "U29") (pin "18") (pinfunction "B4_18") (pintype "unspecified"))
    )
    (net (code "89") (name "PB4") (class "Default")
      (node (ref "U20") (pin "90") (pinfunction "PB4_90") (pintype "bidirectional"))
      (node (ref "U29") (pin "17") (pinfunction "B5_17") (pintype "unspecified"))
    )
    (net (code "90") (name "PB5") (class "Default")
      (node (ref "U20") (pin "91") (pinfunction "PB5_91") (pintype "bidirectional"))
      (node (ref "U29") (pin "16") (pinfunction "B6_16") (pintype "unspecified"))
    )
    (net (code "91") (name "PB6") (class "Default")
      (node (ref "U20") (pin "92") (pinfunction "PB6_92") (pintype "bidirectional"))
      (node (ref "U29") (pin "15") (pinfunction "B7_15") (pintype "unspecified"))
    )
    (net (code "92") (name "PB7") (class "Default")
      (node (ref "U20") (pin "93") (pinfunction "PB7_93") (pintype "bidirectional"))
      (node (ref "U29") (pin "14") (pinfunction "B8_14") (pintype "unspecified"))
    )
    (net (code "93") (name "PB8") (class "Default")
      (node (ref "U20") (pin "95") (pinfunction "PB8_95") (pintype "bidirectional"))
      (node (ref "U29") (pin "22") (pinfunction "OE#_22") (pintype "unspecified"))
    )
    (net (code "94") (name "PB9") (class "Default")
      (node (ref "U20") (pin "96") (pinfunction "PB9_96") (pintype "bidirectional"))
      (node (ref "U29") (pin "2") (pinfunction "DIR_2") (pintype "unspecified"))
    )
    (net (code "95") (name "PD12") (class "Default")
      (node (ref "R51") (pin "2") (pinfunction "2_2") (pintype "input"))
      (node (ref "U20") (pin "59") (pinfunction "PD12_59") (pintype "bidirectional"))
    )
    (net (code "96") (name "PD13") (class "Default")
      (node (ref "R52") (pin "2") (pinfunction "2_2") (pintype "input"))
      (node (ref "U20") (pin "60") (pinfunction "PD13_60") (pintype "bidirectional"))
    )
    (net (code "97") (name "PD14") (class "Default")
      (node (ref "R53") (pin "2") (pinfunction "2_2") (pintype "input"))
      (node (ref "U20") (pin "61") (pinfunction "PD14_61") (pintype "bidirectional"))
    )
    (net (code "98") (name "PD15") (class "Default")
      (node (ref "R54") (pin "2") (pinfunction "2_2") (pintype "input"))
      (node (ref "U20") (pin "62") (pinfunction "PD15_62") (pintype "bidirectional"))
    )
    (net (code "99") (name "RF_INT") (class "Default")
      (node (ref "U20") (pin "55") (pinfunction "PD8_55") (pintype "bidirectional"))
    )
    (net (code "100") (name "RF_PWR_EN") (class "Default")
      (node (ref "R28") (pin "1") (pinfunction "1_1") (pintype "input"))
      (node (ref "U20") (pin "58") (pinfunction "PD11_58") (pintype "bidirectional"))
      (node (ref "U3") (pin "3") (pinfunction "EN_3") (pintype "unspecified"))
    )
    (net (code "101") (name "RF_RST") (class "Default")
      (node (ref "U20") (pin "57") (pinfunction "PD10_57") (pintype "bidirectional"))
    )
    (net (code "102") (name "RF_SPI_CS") (class "Default")
      (node (ref "U20") (pin "56") (pinfunction "PD9_56") (pintype "bidirectional"))
    )
    (net (code "103") (name "RF_VDD") (class "Default")
      (node (ref "C44") (pin "2") (pinfunction "2_2") (pintype "input"))
      (node (ref "C45") (pin "2") (pinfunction "2_2") (pintype "input"))
      (node (ref "C46") (pin "2") (pinfunction "2_2") (pintype "input"))
      (node (ref "R7") (pin "2") (pinfunction "2_2") (pintype "input"))
      (node (ref "U3") (pin "5") (pinfunction "VOUT_5") (pintype "unspecified"))
    )
    (net (code "104") (name "RS485_DIR") (class "Default")
      (node (ref "U20") (pin "67") (pinfunction "PA8_67") (pintype "bidirectional"))
    )
    (net (code "105") (name "SPI_CLK") (class "Default")
      (node (ref "U19") (pin "6") (pinfunction "CLK_6") (pintype "unspecified"))
      (node (ref "U20") (pin "52") (pinfunction "PB13_52") (pintype "bidirectional"))
    )
    (net (code "106") (name "SPI_MISO") (class "Default")
      (node (ref "U19") (pin "2") (pinfunction "DO_2") (pintype "unspecified"))
      (node (ref "U20") (pin "53") (pinfunction "PB14_53") (pintype "bidirectional"))
    )
    (net (code "107") (name "SPI_MOSI") (class "Default")
      (node (ref "U19") (pin "5") (pinfunction "DI_5") (pintype "unspecified"))
      (node (ref "U20") (pin "54") (pinfunction "PB15_54") (pintype "bidirectional"))
    )
    (net (code "108") (name "SRAM_A0") (class "Default")
      (node (ref "U20") (pin "97") (pinfunction "PE0_97") (pintype "bidirectional"))
      (node (ref "U22") (pin "1") (pinfunction "A0_1") (pintype "unspecified"))
    )
    (net (code "109") (name "SRAM_A1") (class "Default")
      (node (ref "U20") (pin "98") (pinfunction "PE1_98") (pintype "bidirectional"))
      (node (ref "U22") (pin "2") (pinfunction "A1_2") (pintype "unspecified"))
    )
    (net (code "110") (name "SRAM_A2") (class "Default")
      (node (ref "U20") (pin "1") (pinfunction "PE2_1") (pintype "bidirectional"))
      (node (ref "U22") (pin "3") (pinfunction "A2_3") (pintype "unspecified"))
    )
    (net (code "111") (name "SRAM_A3") (class "Default")
      (node (ref "U20") (pin "2") (pinfunction "PE3_2") (pintype "bidirectional"))
      (node (ref "U22") (pin "4") (pinfunction "A3_4") (pintype "unspecified"))
    )
    (net (code "112") (name "SRAM_A4") (class "Default")
      (node (ref "U20") (pin "3") (pinfunction "PE4_3") (pintype "bidirectional"))
      (node (ref "U22") (pin "13") (pinfunction "A4_13") (pintype "unspecified"))
    )
    (net (code "113") (name "SRAM_A5") (class "Default")
      (node (ref "U20") (pin "4") (pinfunction "PE5_4") (pintype "bidirectional"))
      (node (ref "U22") (pin "14") (pinfunction "A5_14") (pintype "unspecified"))
    )
    (net (code "114") (name "SRAM_A6") (class "Default")
      (node (ref "U20") (pin "5") (pinfunction "PE6_5") (pintype "bidirectional"))
      (node (ref "U22") (pin "15") (pinfunction "A6_15") (pintype "unspecified"))
    )
    (net (code "115") (name "SRAM_A7") (class "Default")
      (node (ref "U20") (pin "38") (pinfunction "PE7_38") (pintype "bidirectional"))
      (node (ref "U22") (pin "16") (pinfunction "A7_16") (pintype "unspecified"))
    )
    (net (code "116") (name "SRAM_A8") (class "Default")
      (node (ref "U20") (pin "39") (pinfunction "PE8_39") (pintype "bidirectional"))
      (node (ref "U22") (pin "17") (pinfunction "A8_17") (pintype "unspecified"))
    )
    (net (code "117") (name "SRAM_A9") (class "Default")
      (node (ref "U20") (pin "40") (pinfunction "PE9_40") (pintype "bidirectional"))
      (node (ref "U22") (pin "18") (pinfunction "A9_18") (pintype "unspecified"))
    )
    (net (code "118") (name "SRAM_A10") (class "Default")
      (node (ref "U20") (pin "41") (pinfunction "PE10_41") (pintype "bidirectional"))
      (node (ref "U22") (pin "19") (pinfunction "A10_19") (pintype "unspecified"))
    )
    (net (code "119") (name "SRAM_A11") (class "Default")
      (node (ref "U20") (pin "42") (pinfunction "PE11_42") (pintype "bidirectional"))
      (node (ref "U22") (pin "20") (pinfunction "A11_20") (pintype "unspecified"))
    )
    (net (code "120") (name "SRAM_A12") (class "Default")
      (node (ref "U20") (pin "43") (pinfunction "PE12_43") (pintype "bidirectional"))
      (node (ref "U22") (pin "21") (pinfunction "A12_21") (pintype "unspecified"))
    )
    (net (code "121") (name "SRAM_A13") (class "Default")
      (node (ref "U20") (pin "44") (pinfunction "PE13_44") (pintype "bidirectional"))
      (node (ref "U22") (pin "29") (pinfunction "A13_29") (pintype "unspecified"))
    )
    (net (code "122") (name "SRAM_A14") (class "Default")
      (node (ref "U20") (pin "45") (pinfunction "PE14_45") (pintype "bidirectional"))
      (node (ref "U22") (pin "30") (pinfunction "A14_30") (pintype "unspecified"))
    )
    (net (code "123") (name "SRAM_A15") (class "Default")
      (node (ref "U20") (pin "46") (pinfunction "PE15_46") (pintype "bidirectional"))
      (node (ref "U22") (pin "31") (pinfunction "A15_31") (pintype "unspecified"))
    )
    (net (code "124") (name "SRAM_A16") (class "Default")
      (node (ref "U20") (pin "77") (pinfunction "PA15_77") (pintype "bidirectional"))
      (node (ref "U22") (pin "32") (pinfunction "A16_32") (pintype "unspecified"))
    )
    (net (code "125") (name "SRAM_CE#") (class "Default")
      (node (ref "R2") (pin "1") (pinfunction "1_1") (pintype "input"))
      (node (ref "U20") (pin "15") (pinfunction "PC0_15") (pintype "bidirectional"))
      (node (ref "U22") (pin "5") (pinfunction "CE#_5") (pintype "unspecified"))
    )
    (net (code "126") (name "SRAM_D0") (class "Default")
      (node (ref "U20") (pin "81") (pinfunction "PD0_81") (pintype "bidirectional"))
      (node (ref "U22") (pin "6") (pinfunction "I/O0_6") (pintype "unspecified"))
    )
    (net (code "127") (name "SRAM_D1") (class "Default")
      (node (ref "U20") (pin "82") (pinfunction "PD1_82") (pintype "bidirectional"))
      (node (ref "U22") (pin "7") (pinfunction "I/O1_7") (pintype "unspecified"))
    )
    (net (code "128") (name "SRAM_D2") (class "Default")
      (node (ref "U20") (pin "83") (pinfunction "PD2_83") (pintype "bidirectional"))
      (node (ref "U22") (pin "10") (pinfunction "I/O2_10") (pintype "unspecified"))
    )
    (net (code "129") (name "SRAM_D3") (class "Default")
      (node (ref "U20") (pin "84") (pinfunction "PD3_84") (pintype "bidirectional"))
      (node (ref "U22") (pin "11") (pinfunction "I/O3_11") (pintype "unspecified"))
    )
    (net (code "130") (name "SRAM_D4") (class "Default")
      (node (ref "U20") (pin "85") (pinfunction "PD4_85") (pintype "bidirectional"))
      (node (ref "U22") (pin "22") (pinfunction "I/O4_22") (pintype "unspecified"))
    )
    (net (code "131") (name "SRAM_D5") (class "Default")
      (node (ref "U20") (pin "86") (pinfunction "PD5_86") (pintype "bidirectional"))
      (node (ref "U22") (pin "23") (pinfunction "I/O5_23") (pintype "unspecified"))
    )
    (net (code "132") (name "SRAM_D6") (class "Default")
      (node (ref "U20") (pin "87") (pinfunction "PD6_87") (pintype "bidirectional"))
      (node (ref "U22") (pin "26") (pinfunction "I/O6_26") (pintype "unspecified"))
    )
    (net (code "133") (name "SRAM_D7") (class "Default")
      (node (ref "U20") (pin "88") (pinfunction "PD7_88") (pintype "bidirectional"))
      (node (ref "U22") (pin "27") (pinfunction "I/O7_27") (pintype "unspecified"))
    )
    (net (code "134") (name "SRAM_OE#") (class "Default")
      (node (ref "U20") (pin "17") (pinfunction "PC2_17") (pintype "bidirectional"))
      (node (ref "U22") (pin "28") (pinfunction "OE#_28") (pintype "unspecified"))
    )
    (net (code "135") (name "SRAM_WE#") (class "Default")
      (node (ref "U20") (pin "16") (pinfunction "PC1_16") (pintype "bidirectional"))
      (node (ref "U22") (pin "12") (pinfunction "WE#_12") (pintype "unspecified"))
    )
    (net (code "136") (name "USART_RX") (class "Default")
      (node (ref "U20") (pin "69") (pinfunction "PA10_69") (pintype "bidirectional"))
    )
    (net (code "137") (name "USART_TX") (class "Default")
      (node (ref "U20") (pin "68") (pinfunction "PA9_68") (pintype "bidirectional"))
    )
    (net (code "138") (name "VDD") (class "Default")
      (node (ref "C16") (pin "2") (pinfunction "2_2") (pintype "input"))
      (node (ref "C17") (pin "2") (pinfunction "2_2") (pintype "input"))
      (node (ref "C2") (pin "2") (pinfunction "2_2") (pintype "input"))
      (node (ref "C24") (pin "1") (pinfunction "1_1") (pintype "input"))
      (node (ref "C3") (pin "2") (pinfunction "2_2") (pintype "input"))
      (node (ref "C33") (pin "2") (pinfunction "2_2") (pintype "input"))
      (node (ref "C4") (pin "2") (pinfunction "2_2") (pintype "input"))
      (node (ref "C49") (pin "1") (pinfunction "1_1") (pintype "input"))
      (node (ref "C5") (pin "2") (pinfunction "2_2") (pintype "input"))
      (node (ref "C52") (pin "2") (pinfunction "2_2") (pintype "input"))
      (node (ref "C53") (pin "2") (pinfunction "2_2") (pintype "input"))
      (node (ref "C54") (pin "2") (pinfunction "2_2") (pintype "input"))
      (node (ref "C55") (pin "2") (pinfunction "2_2") (pintype "input"))
      (node (ref "C56") (pin "2") (pinfunction "2_2") (pintype "input"))
      (node (ref "H1") (pin "1") (pinfunction "1_1") (pintype "unspecified"))
      (node (ref "L2") (pin "1") (pinfunction "1_1") (pintype "unspecified"))
      (node (ref "P1") (pin "1") (pinfunction "1_1") (pintype "unspecified"))
      (node (ref "R1") (pin "2") (pinfunction "2_2") (pintype "input"))
      (node (ref "R11") (pin "1") (pinfunction "1_1") (pintype "input"))
      (node (ref "R2") (pin "2") (pinfunction "2_2") (pintype "input"))
      (node (ref "R26") (pin "2") (pinfunction "2_2") (pintype "input"))
      (node (ref "R3") (pin "2") (pinfunction "2_2") (pintype "input"))
      (node (ref "R4") (pin "1") (pinfunction "1_1") (pintype "input"))
      (node (ref "R63") (pin "2") (pinfunction "2_2") (pintype "input"))
      (node (ref "R64") (pin "2") (pinfunction "2_2") (pintype "input"))
      (node (ref "R65") (pin "2") (pinfunction "2_2") (pintype "input"))
      (node (ref "R66") (pin "2") (pinfunction "2_2") (pintype "input"))
      (node (ref "R67") (pin "2") (pinfunction "2_2") (pintype "input"))
      (node (ref "U19") (pin "7") (pinfunction "IO3_7") (pintype "unspecified"))
      (node (ref "U19") (pin "8") (pinfunction "VCC_8") (pintype "unspecified"))
      (node (ref "U2") (pin "5") (pinfunction "VOUT_5") (pintype "unspecified"))
      (node (ref "U20") (pin "100") (pinfunction "VDD_3_100") (pintype "unspecified"))
      (node (ref "U20") (pin "11") (pinfunction "VDD_5_11") (pintype "unspecified"))
      (node (ref "U20") (pin "28") (pinfunction "VDD_4_28") (pintype "unspecified"))
      (node (ref "U20") (pin "50") (pinfunction "VDD_1_50") (pintype "unspecified"))
      (node (ref "U20") (pin "6") (pinfunction "VBAT_6") (pintype "unspecified"))
      (node (ref "U20") (pin "75") (pinfunction "VDD_2_75") (pintype "unspecified"))
      (node (ref "U22") (pin "8") (pinfunction "VDD_8") (pintype "unspecified"))
      (node (ref "U29") (pin "23") (pinfunction "VCCB_23") (pintype "unspecified"))
      (node (ref "U29") (pin "24") (pinfunction "VCCB_24") (pintype "unspecified"))
    )
    (net (code "139") (name "VIN1+") (class "Default")
      (node (ref "CN1") (pin "1") (pinfunction "1_1") (pintype "unspecified"))
      (node (ref "R14") (pin "1") (pinfunction "1_1") (pintype "input"))
    )
    (net (code "140") (name "VIN2+") (class "Default")
      (node (ref "CN2") (pin "1") (pinfunction "1_1") (pintype "unspecified"))
      (node (ref "R16") (pin "1") (pinfunction "1_1") (pintype "input"))
    )
    (net (code "141") (name "VIN3+") (class "Default")
      (node (ref "CN3") (pin "1") (pinfunction "1_1") (pintype "unspecified"))
      (node (ref "R20") (pin "1") (pinfunction "1_1") (pintype "input"))
    )
    (net (code "142") (name "VIN4+") (class "Default")
      (node (ref "CN4") (pin "1") (pinfunction "1_1") (pintype "unspecified"))
      (node (ref "R22") (pin "1") (pinfunction "1_1") (pintype "input"))
    )
    (net (code "144") (name "VREF") (class "Default")
      (node (ref "C48") (pin "2") (pinfunction "2_2") (pintype "input"))
      (node (ref "U20") (pin "21") (pinfunction "VREF+_21") (pintype "unspecified"))
      (node (ref "U4") (pin "6") (pinfunction "VOUT_6") (pintype "unspecified"))
    )
    (net (code "145") (name "unconnected-(C18-Pad1)") (class "Default")
      (node (ref "C18") (pin "1") (pinfunction "1_1") (pintype "input"))
    )
    (net (code "146") (name "unconnected-(C18-Pad2)") (class "Default")
      (node (ref "C18") (pin "2") (pinfunction "2_2") (pintype "input"))
    )
    (net (code "147") (name "unconnected-(C19-Pad1)") (class "Default")
      (node (ref "C19") (pin "1") (pinfunction "1_1") (pintype "input"))
    )
    (net (code "148") (name "unconnected-(C19-Pad2)") (class "Default")
      (node (ref "C19") (pin "2") (pinfunction "2_2") (pintype "input"))
    )
    (net (code "149") (name "unconnected-(C20-Pad2)") (class "Default")
      (node (ref "C20") (pin "2") (pinfunction "2_2") (pintype "input"))
    )
    (net (code "150") (name "unconnected-(C21-Pad2)") (class "Default")
      (node (ref "C21") (pin "2") (pinfunction "2_2") (pintype "input"))
    )
    (net (code "151") (name "unconnected-(C22-Pad1)") (class "Default")
      (node (ref "C22") (pin "1") (pinfunction "1_1") (pintype "input"))
    )
    (net (code "152") (name "unconnected-(C22-Pad2)") (class "Default")
      (node (ref "C22") (pin "2") (pinfunction "2_2") (pintype "input"))
    )
    (net (code "153") (name "unconnected-(C39-Pad1)") (class "Default")
      (node (ref "C39") (pin "1") (pinfunction "1_1") (pintype "input"))
    )
    (net (code "154") (name "unconnected-(C39-Pad2)") (class "Default")
      (node (ref "C39") (pin "2") (pinfunction "2_2") (pintype "input"))
    )
    (net (code "155") (name "unconnected-(C40-Pad1)") (class "Default")
      (node (ref "C40") (pin "1") (pinfunction "1_1") (pintype "input"))
    )
    (net (code "156") (name "unconnected-(C40-Pad2)") (class "Default")
      (node (ref "C40") (pin "2") (pinfunction "2_2") (pintype "input"))
    )
    (net (code "157") (name "unconnected-(C41-Pad1)") (class "Default")
      (node (ref "C41") (pin "1") (pinfunction "1_1") (pintype "input"))
    )
    (net (code "158") (name "unconnected-(C41-Pad2)") (class "Default")
      (node (ref "C41") (pin "2") (pinfunction "2_2") (pintype "input"))
    )
    (net (code "159") (name "unconnected-(CN14-Pad1)") (class "Default")
      (node (ref "CN14") (pin "1") (pinfunction "1_1") (pintype "unspecified"))
    )
    (net (code "160") (name "unconnected-(CN14-Pad2)") (class "Default")
      (node (ref "CN14") (pin "2") (pinfunction "2_2") (pintype "unspecified"))
    )
    (net (code "161") (name "unconnected-(CN14-Pad3)") (class "Default")
      (node (ref "CN14") (pin "3") (pinfunction "3_3") (pintype "unspecified"))
    )
    (net (code "162") (name "unconnected-(D2-Pad1)") (class "Default")
      (node (ref "D2") (pin "1") (pinfunction "1_1") (pintype "unspecified"))
    )
    (net (code "163") (name "unconnected-(D2-Pad2)") (class "Default")
      (node (ref "D2") (pin "2") (pinfunction "2_2") (pintype "unspecified"))
    )
    (net (code "164") (name "unconnected-(D3-Pad1)") (class "Default")
      (node (ref "D3") (pin "1") (pinfunction "1_1") (pintype "unspecified"))
    )
    (net (code "165") (name "unconnected-(D3-Pad2)") (class "Default")
      (node (ref "D3") (pin "2") (pinfunction "2_2") (pintype "unspecified"))
    )
    (net (code "166") (name "unconnected-(D4-Pad1)") (class "Default")
      (node (ref "D4") (pin "1") (pinfunction "1_1") (pintype "unspecified"))
    )
    (net (code "167") (name "unconnected-(D4-Pad2)") (class "Default")
      (node (ref "D4") (pin "2") (pinfunction "2_2") (pintype "unspecified"))
    )
    (net (code "168") (name "unconnected-(L4-Pad1)") (class "Default")
      (node (ref "L4") (pin "1") (pinfunction "1_1") (pintype "unspecified"))
    )
    (net (code "169") (name "unconnected-(L4-Pad2)") (class "Default")
      (node (ref "L4") (pin "2") (pinfunction "2_2") (pintype "unspecified"))
    )
    (net (code "170") (name "unconnected-(R9-Pad1)") (class "Default")
      (node (ref "R9") (pin "1") (pinfunction "1_1") (pintype "input"))
    )
    (net (code "171") (name "unconnected-(R42-Pad1)") (class "Default")
      (node (ref "R42") (pin "1") (pinfunction "1_1") (pintype "input"))
    )
    (net (code "172") (name "unconnected-(R42-Pad2)") (class "Default")
      (node (ref "R42") (pin "2") (pinfunction "2_2") (pintype "input"))
    )
    (net (code "173") (name "unconnected-(R43-Pad1)") (class "Default")
      (node (ref "R43") (pin "1") (pinfunction "1_1") (pintype "input"))
    )
    (net (code "174") (name "unconnected-(R43-Pad2)") (class "Default")
      (node (ref "R43") (pin "2") (pinfunction "2_2") (pintype "input"))
    )
    (net (code "175") (name "unconnected-(R44-Pad1)") (class "Default")
      (node (ref "R44") (pin "1") (pinfunction "1_1") (pintype "input"))
    )
    (net (code "176") (name "unconnected-(R44-Pad2)") (class "Default")
      (node (ref "R44") (pin "2") (pinfunction "2_2") (pintype "input"))
    )
    (net (code "177") (name "unconnected-(R45-Pad1)") (class "Default")
      (node (ref "R45") (pin "1") (pinfunction "1_1") (pintype "input"))
    )
    (net (code "178") (name "unconnected-(R45-Pad2)") (class "Default")
      (node (ref "R45") (pin "2") (pinfunction "2_2") (pintype "input"))
    )
    (net (code "179") (name "unconnected-(R46-Pad1)") (class "Default")
      (node (ref "R46") (pin "1") (pinfunction "1_1") (pintype "input"))
    )
    (net (code "180") (name "unconnected-(R46-Pad2)") (class "Default")
      (node (ref "R46") (pin "2") (pinfunction "2_2") (pintype "input"))
    )
    (net (code "181") (name "unconnected-(R47-Pad1)") (class "Default")
      (node (ref "R47") (pin "1") (pinfunction "1_1") (pintype "input"))
    )
    (net (code "182") (name "unconnected-(R47-Pad2)") (class "Default")
      (node (ref "R47") (pin "2") (pinfunction "2_2") (pintype "input"))
    )
    (net (code "183") (name "unconnected-(RF1-GND-Pad2)") (class "Default")
      (node (ref "RF1") (pin "2") (pinfunction "GND_2") (pintype "unspecified"))
    )
    (net (code "184") (name "unconnected-(RF1-GND-Pad3)") (class "Default")
      (node (ref "RF1") (pin "3") (pinfunction "GND_3") (pintype "unspecified"))
    )
    (net (code "185") (name "unconnected-(RF1-SIG-Pad1)") (class "Default")
      (node (ref "RF1") (pin "1") (pinfunction "SIG_1") (pintype "unspecified"))
    )
    (net (code "186") (name "unconnected-(U2-NC-Pad4)") (class "Default")
      (node (ref "U2") (pin "4") (pinfunction "NC_4") (pintype "unspecified+no_connect"))
    )
    (net (code "187") (name "unconnected-(U3-NC-Pad4)") (class "Default")
      (node (ref "U3") (pin "4") (pinfunction "NC_4") (pintype "unspecified+no_connect"))
    )
    (net (code "188") (name "unconnected-(U4-NC-Pad1)") (class "Default")
      (node (ref "U4") (pin "1") (pinfunction "NC_1") (pintype "unspecified+no_connect"))
    )
    (net (code "189") (name "unconnected-(U4-NC-Pad7)") (class "Default")
      (node (ref "U4") (pin "7") (pinfunction "NC_7") (pintype "unspecified+no_connect"))
    )
    (net (code "190") (name "unconnected-(U4-NC-Pad8)") (class "Default")
      (node (ref "U4") (pin "8") (pinfunction "NC_8") (pintype "unspecified+no_connect"))
    )
    (net (code "191") (name "unconnected-(U4-TEMP-Pad3)") (class "Default")
      (node (ref "U4") (pin "3") (pinfunction "TEMP_3") (pintype "unspecified+no_connect"))
    )
    (net (code "192") (name "unconnected-(U4-TRIM-Pad5)") (class "Default")
      (node (ref "U4") (pin "5") (pinfunction "TRIM_5") (pintype "unspecified+no_connect"))
    )
    (net (code "193") (name "unconnected-(U20A-NC-Pad73)") (class "Default")
      (node (ref "U20") (pin "73") (pinfunction "NC_73") (pintype "unspecified+no_connect"))
    )
    (net (code "194") (name "unconnected-(U20A-PA11-Pad70)") (class "Default")
      (node (ref "U20") (pin "70") (pinfunction "PA11_70") (pintype "bidirectional+no_connect"))
    )
    (net (code "195") (name "unconnected-(U20A-PA12-Pad71)") (class "Default")
      (node (ref "U20") (pin "71") (pinfunction "PA12_71") (pintype "bidirectional+no_connect"))
    )
    (net (code "196") (name "unconnected-(U20A-PC8-Pad65)") (class "Default")
      (node (ref "U20") (pin "65") (pinfunction "PC8_65") (pintype "bidirectional+no_connect"))
    )
    (net (code "197") (name "unconnected-(U20A-PC9-Pad66)") (class "Default")
      (node (ref "U20") (pin "66") (pinfunction "PC9_66") (pintype "bidirectional+no_connect"))
    )
    (net (code "198") (name "unconnected-(U20A-PC10-Pad78)") (class "Default")
      (node (ref "U20") (pin "78") (pinfunction "PC10_78") (pintype "bidirectional+no_connect"))
    )
    (net (code "199") (name "unconnected-(U20A-PC11-Pad79)") (class "Default")
      (node (ref "U20") (pin "79") (pinfunction "PC11_79") (pintype "bidirectional+no_connect"))
    )
    (net (code "200") (name "unconnected-(U20A-PC12-Pad80)") (class "Default")
      (node (ref "U20") (pin "80") (pinfunction "PC12_80") (pintype "bidirectional+no_connect"))
    )
    (net (code "201") (name "unconnected-(U20A-PC13-TAMPER-RTC-Pad7)") (class "Default")
      (node (ref "U20") (pin "7") (pinfunction "PC13-TAMPER-RTC_7") (pintype "bidirectional+no_connect"))
    )
    (net (code "202") (name "unconnected-(U44-A-Pad12)") (class "Default")
      (node (ref "U44") (pin "12") (pinfunction "A_12") (pintype "unspecified"))
    )
    (net (code "203") (name "unconnected-(U44-B-Pad13)") (class "Default")
      (node (ref "U44") (pin "13") (pinfunction "B_13") (pintype "unspecified"))
    )
    (net (code "204") (name "unconnected-(U44-DE-Pad5)") (class "Default")
      (node (ref "U44") (pin "5") (pinfunction "DE_5") (pintype "unspecified"))
    )
    (net (code "205") (name "unconnected-(U44-DI-Pad6)") (class "Default")
      (node (ref "U44") (pin "6") (pinfunction "DI_6") (pintype "unspecified"))
    )
    (net (code "206") (name "unconnected-(U44-GNDA-Pad2)") (class "Default")
      (node (ref "U44") (pin "2") (pinfunction "GNDA_2") (pintype "unspecified"))
    )
    (net (code "207") (name "unconnected-(U44-GNDA-Pad7)") (class "Default")
      (node (ref "U44") (pin "7") (pinfunction "GNDA_7") (pintype "unspecified"))
    )
    (net (code "208") (name "unconnected-(U44-GNDA-Pad8)") (class "Default")
      (node (ref "U44") (pin "8") (pinfunction "GNDA_8") (pintype "unspecified"))
    )
    (net (code "209") (name "unconnected-(U44-GNDB-Pad9)") (class "Default")
      (node (ref "U44") (pin "9") (pinfunction "GNDB_9") (pintype "unspecified"))
    )
    (net (code "210") (name "unconnected-(U44-GNDB-Pad15)") (class "Default")
      (node (ref "U44") (pin "15") (pinfunction "GNDB_15") (pintype "unspecified"))
    )
    (net (code "211") (name "unconnected-(U44-NC-Pad11)") (class "Default")
      (node (ref "U44") (pin "11") (pinfunction "NC_11") (pintype "unspecified"))
    )
    (net (code "212") (name "unconnected-(U44-NC-Pad14)") (class "Default")
      (node (ref "U44") (pin "14") (pinfunction "NC_14") (pintype "unspecified"))
    )
    (net (code "213") (name "unconnected-(U44-RE#-Pad4)") (class "Default")
      (node (ref "U44") (pin "4") (pinfunction "RE#_4") (pintype "unspecified"))
    )
    (net (code "214") (name "unconnected-(U44-RO-Pad3)") (class "Default")
      (node (ref "U44") (pin "3") (pinfunction "RO_3") (pintype "unspecified"))
    )
    (net (code "215") (name "unconnected-(U44-SEL-Pad10)") (class "Default")
      (node (ref "U44") (pin "10") (pinfunction "SEL_10") (pintype "unspecified"))
    )
    (net (code "216") (name "unconnected-(U44-VISO-Pad16)") (class "Default")
      (node (ref "U44") (pin "16") (pinfunction "VISO_16") (pintype "unspecified"))
    )
    (net (code "217") (name "unconnected-(U44-Vcc-Pad1)") (class "Default")
      (node (ref "U44") (pin "1") (pinfunction "Vcc_1") (pintype "unspecified"))
    )
  )
)
